# 20230822.net
KiCad netlist of a schematic drawn in EAGLE
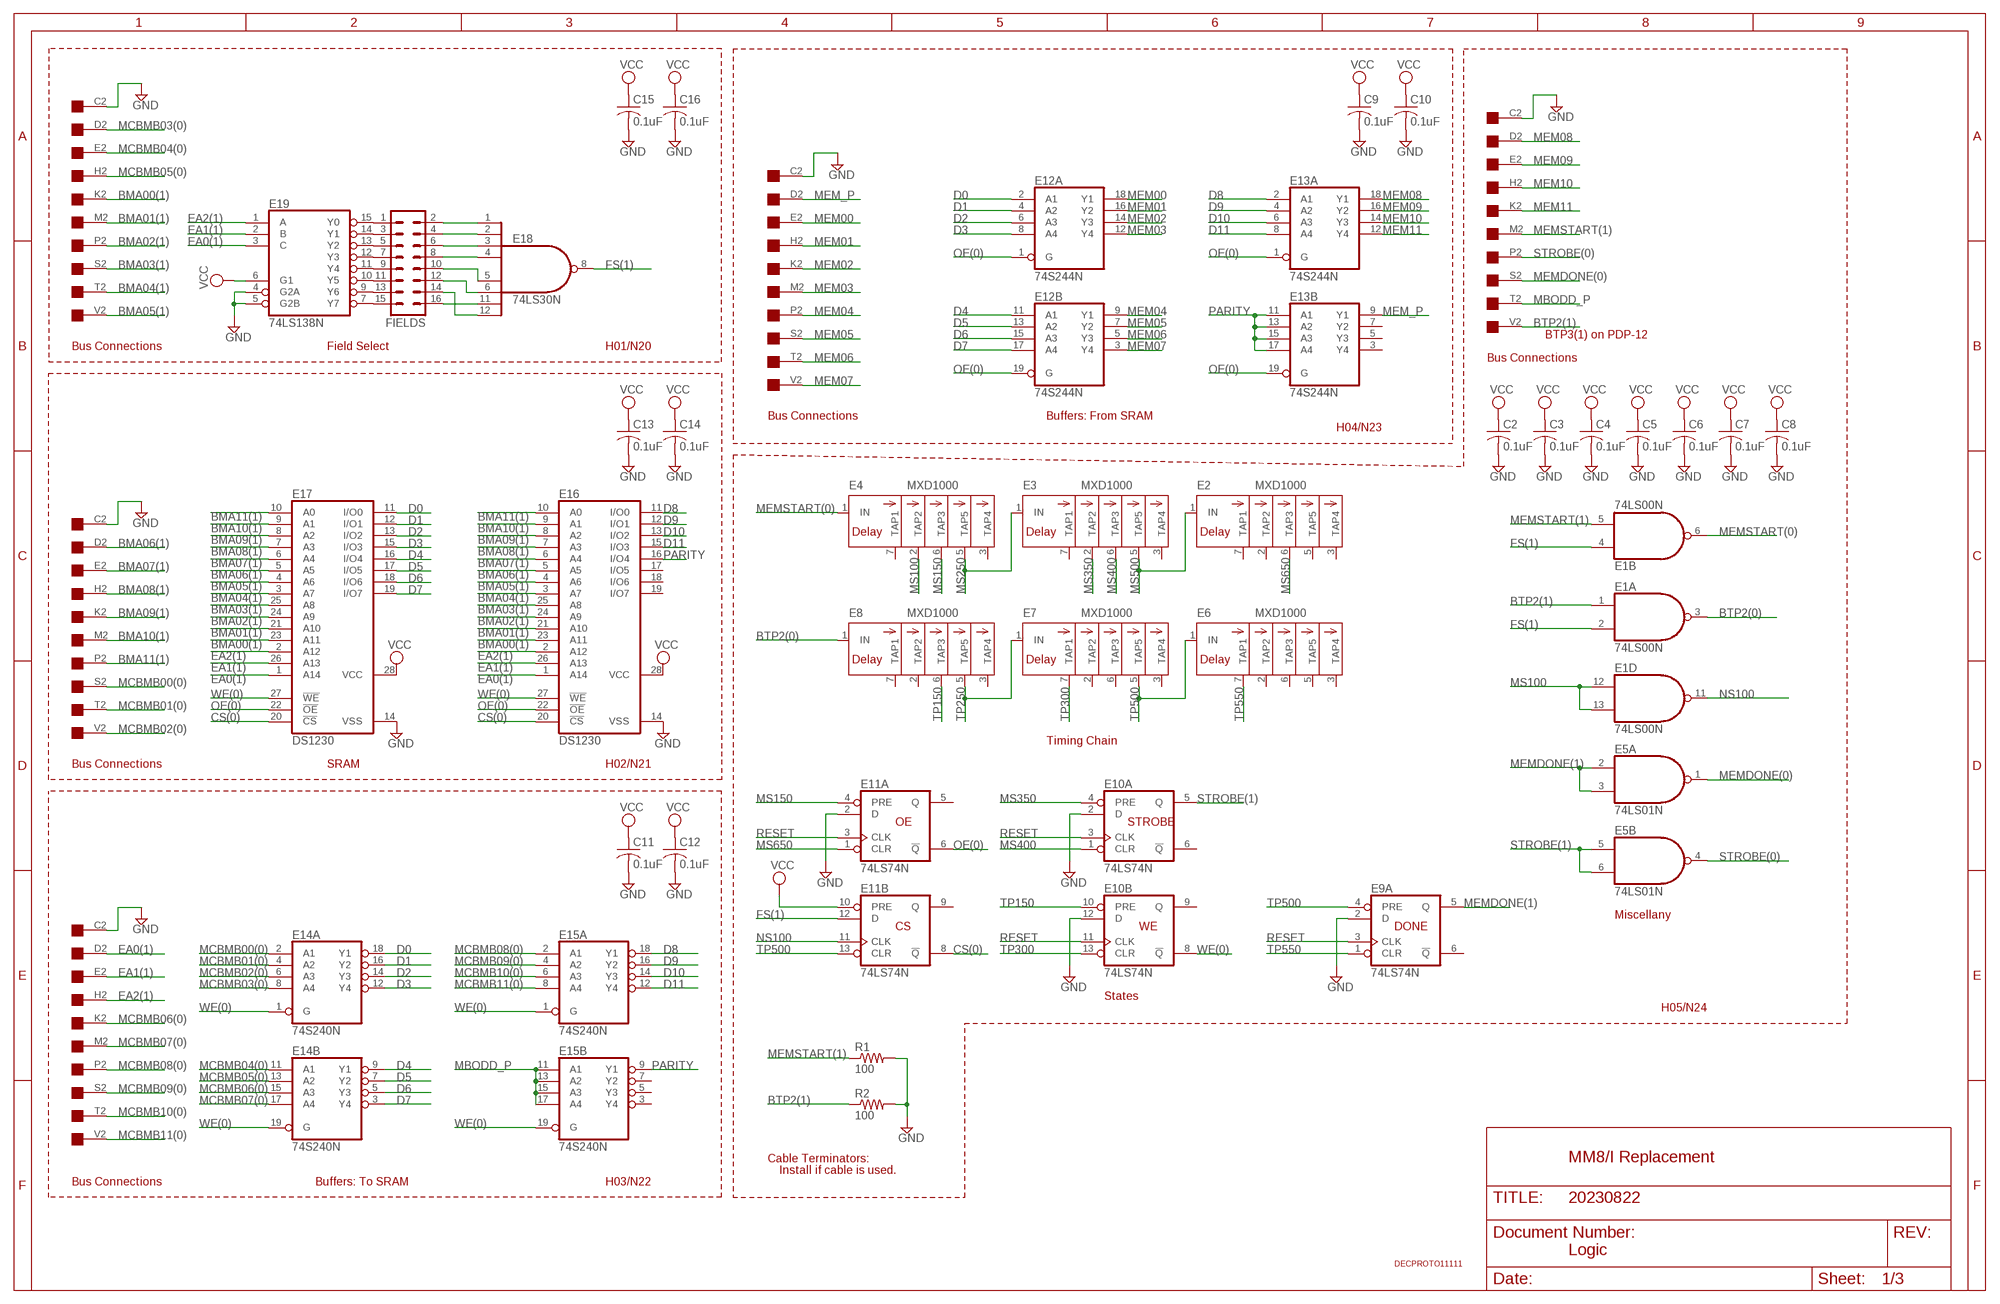
[diagram p0: schematic, sheet 1]
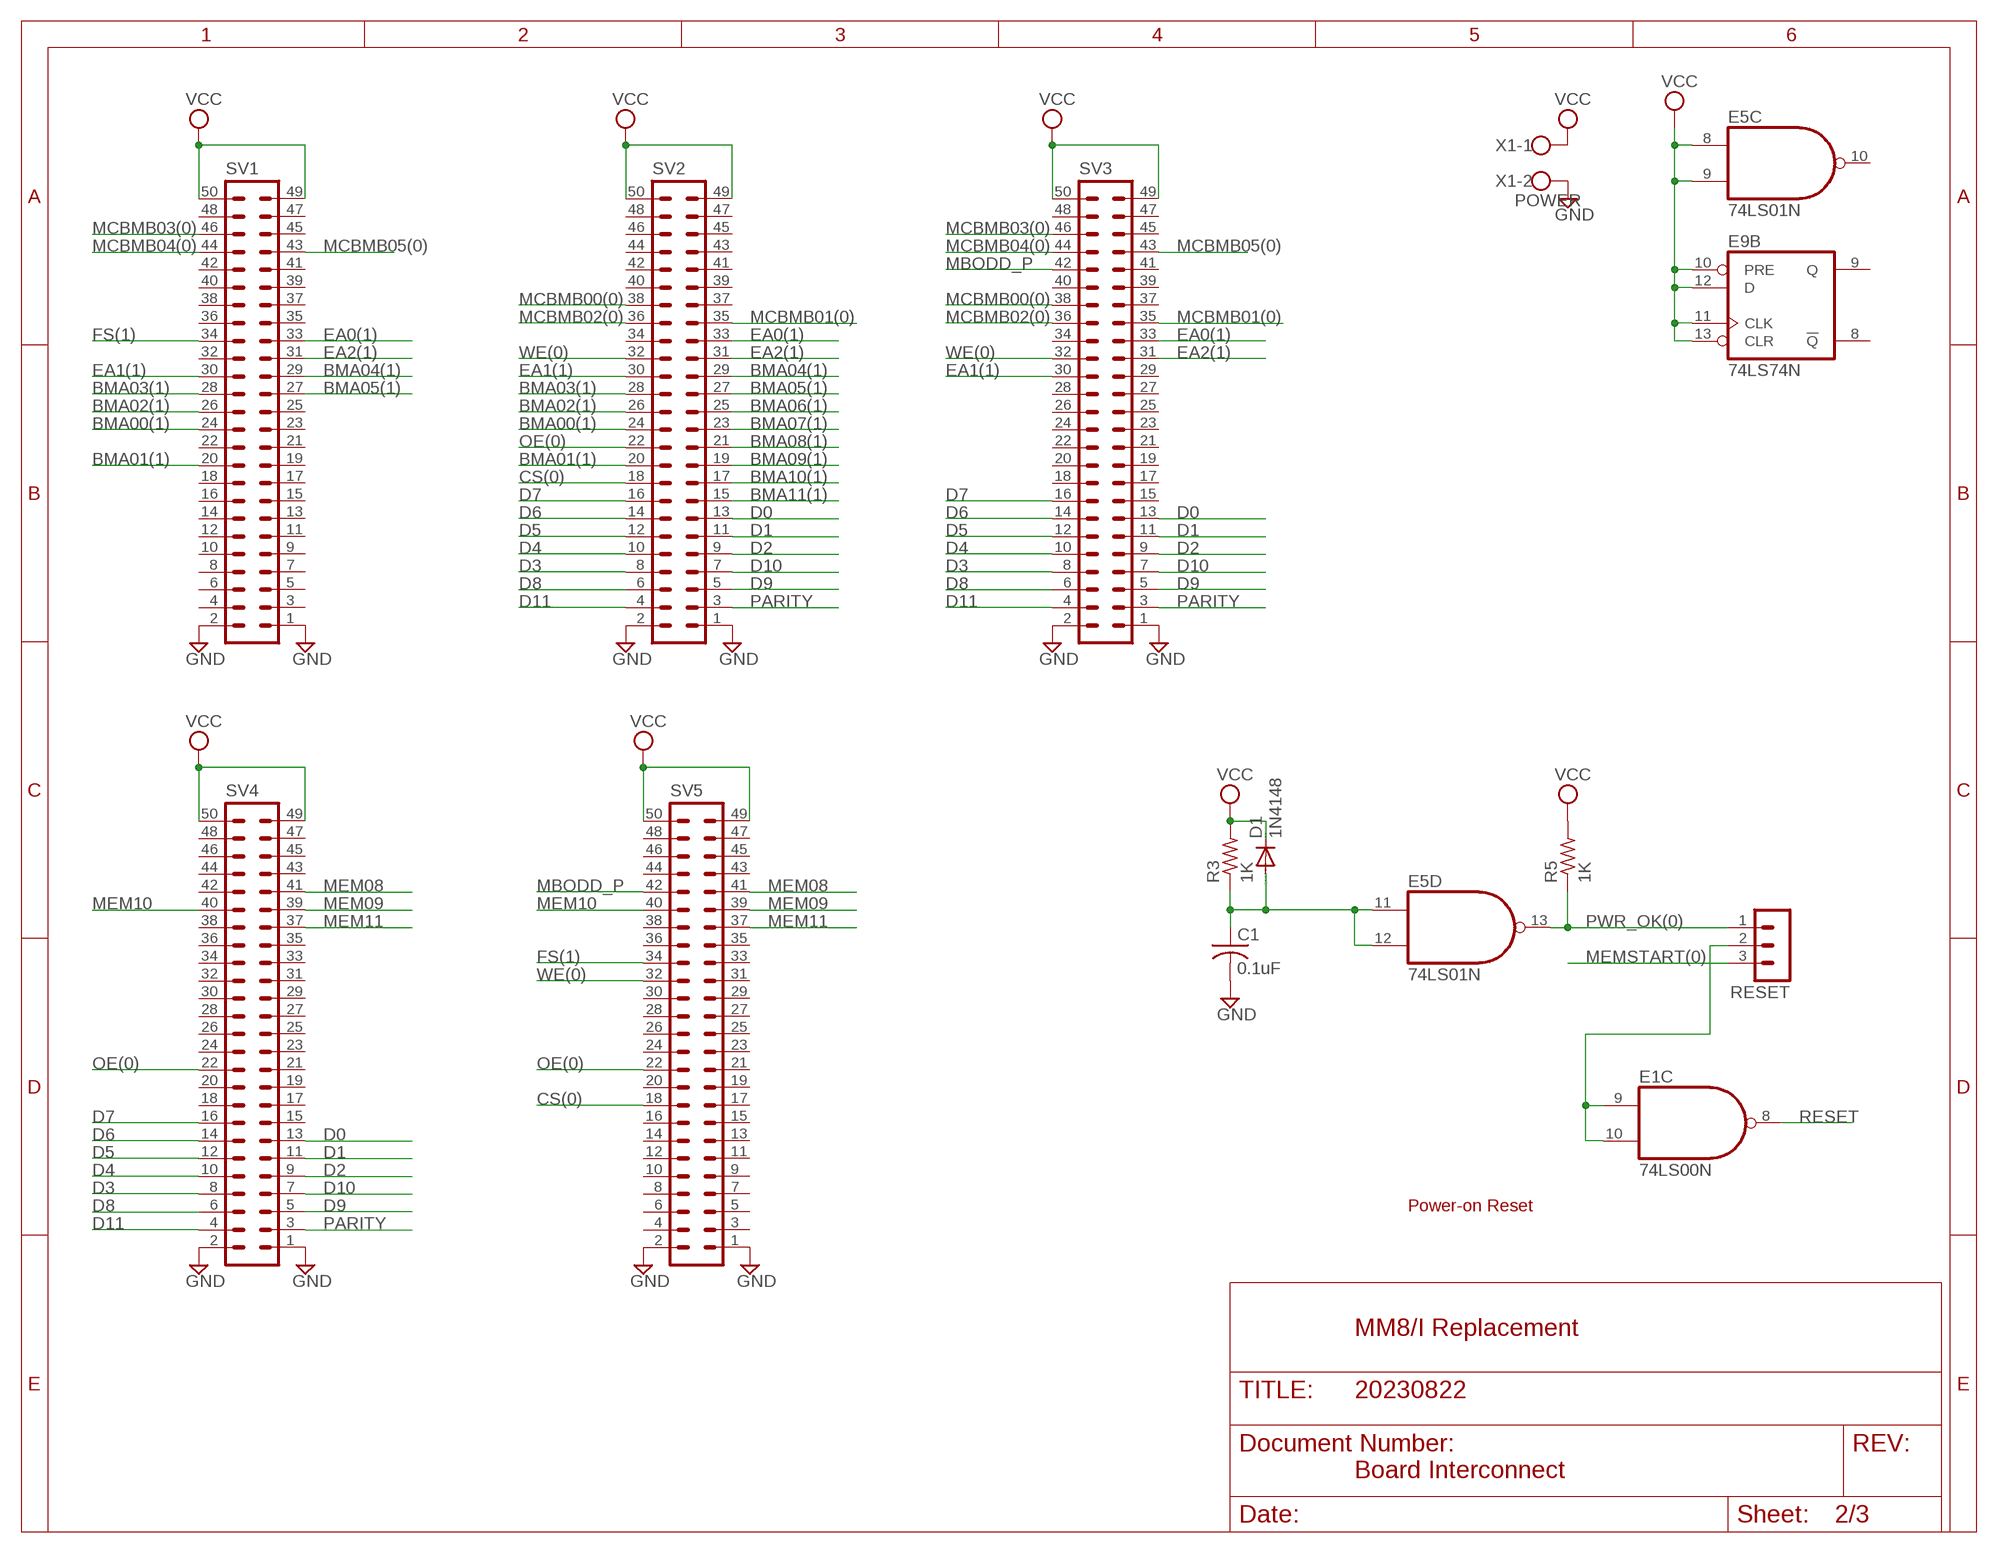
[diagram p1: schematic, sheet 2]
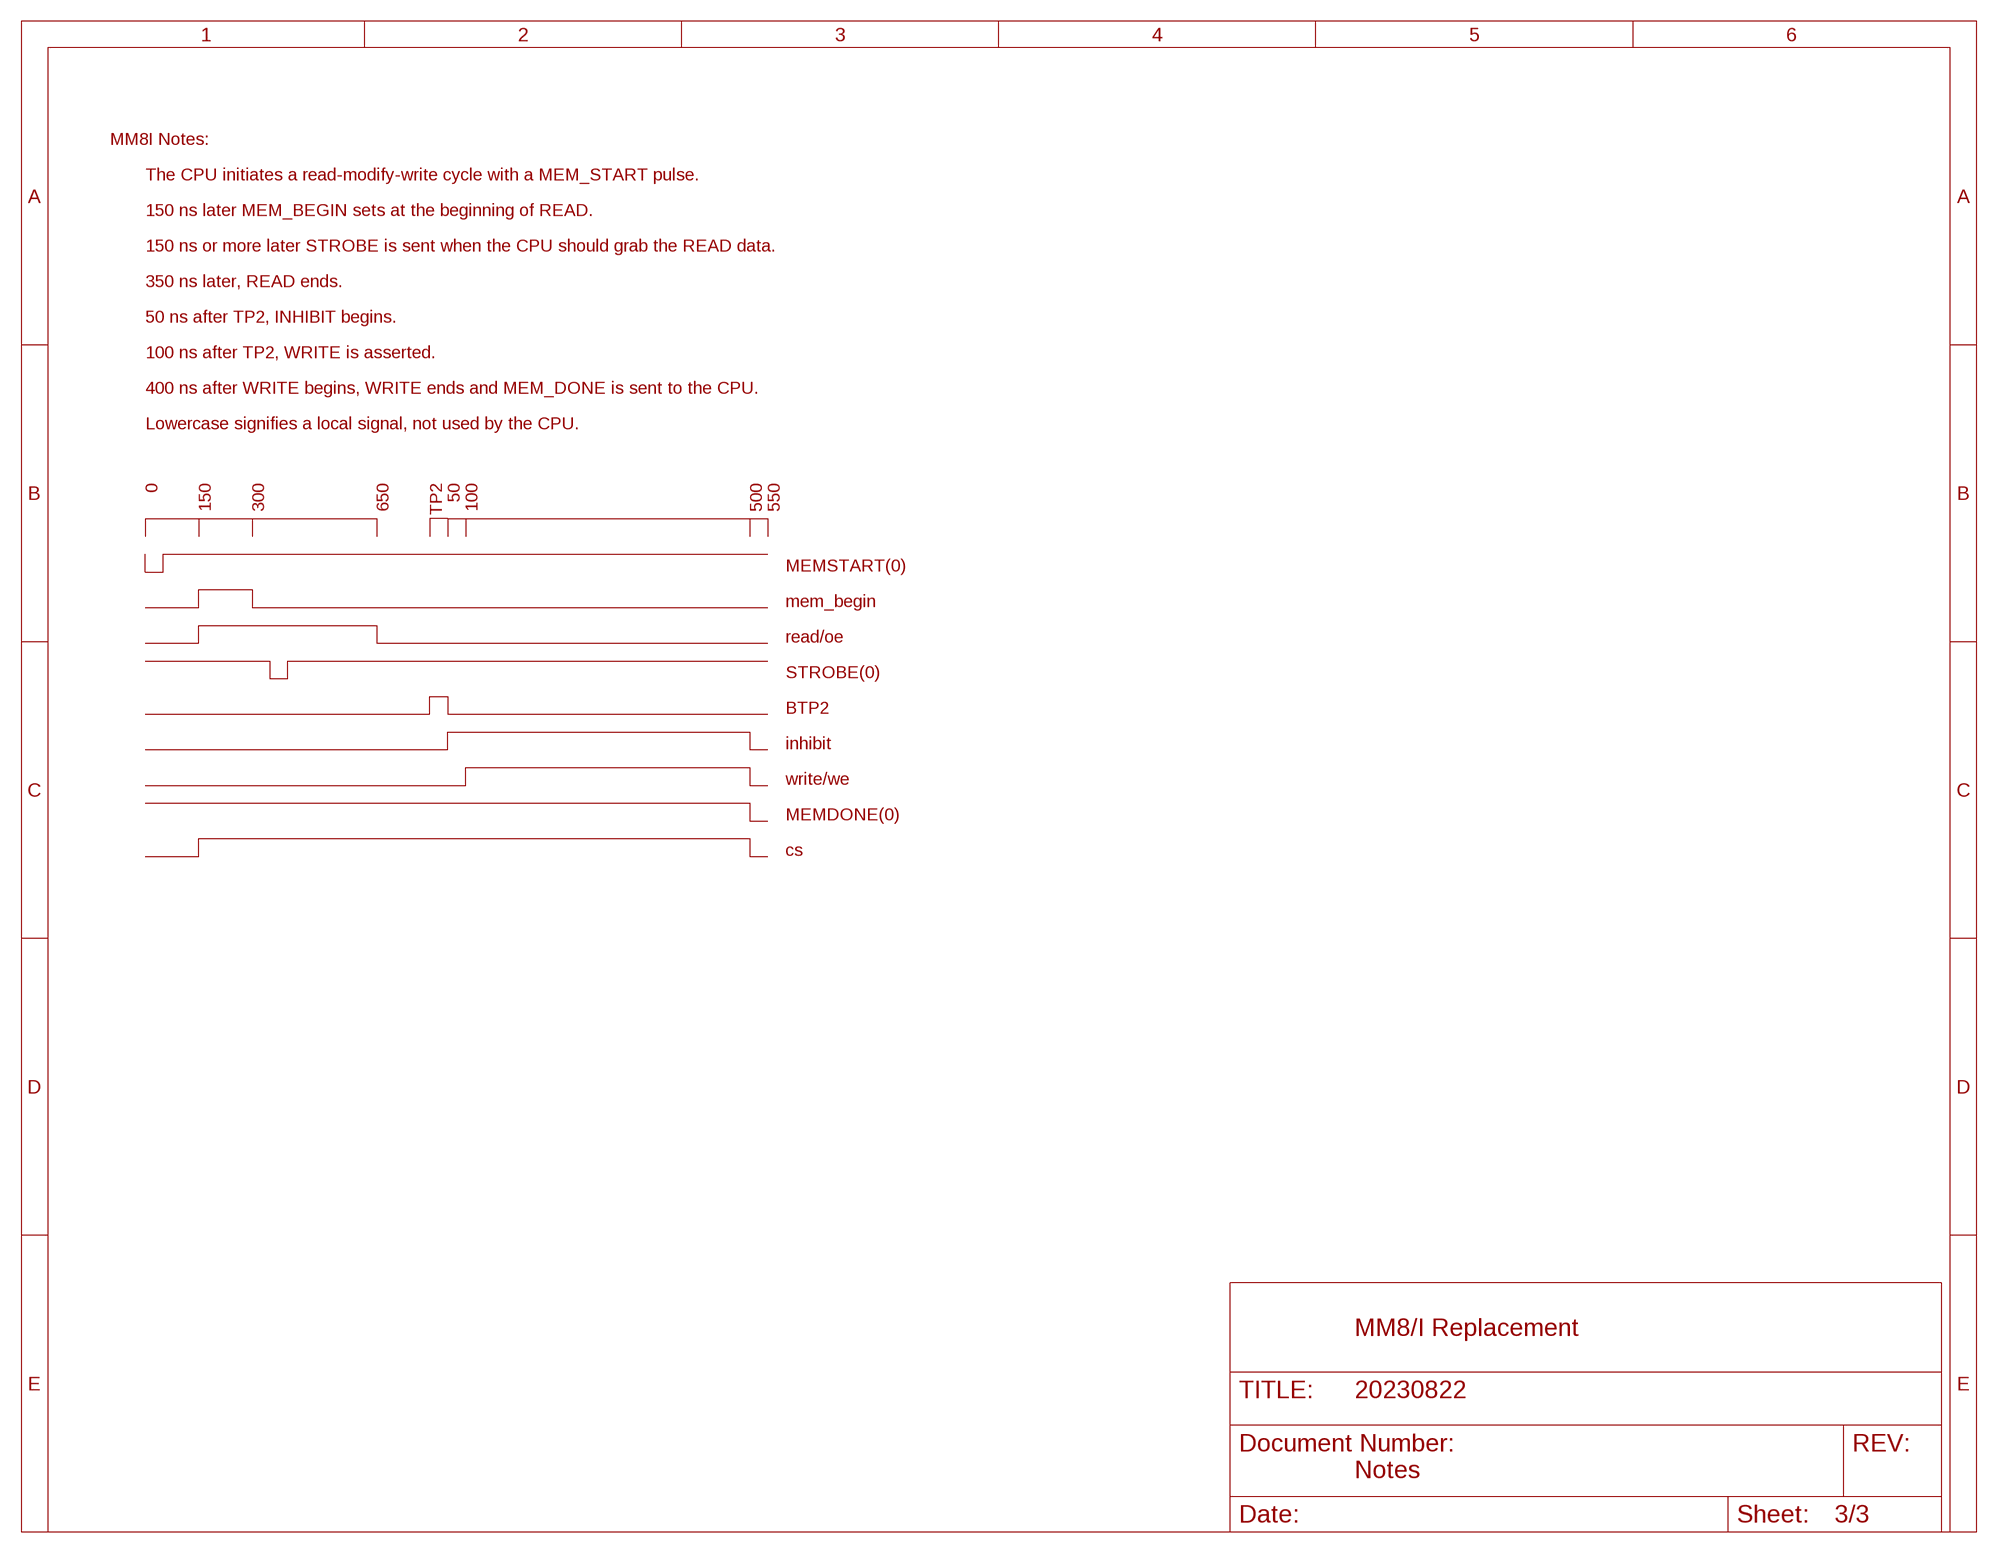
[diagram p2: schematic, sheet 3]

(export (version "E")
  (design (tool "Eeschema 10.0.6"))
  (components
    (comp (ref "C2")
      (value "0.1uF")
      (footprint "eagle-import:C050-025X075")
      (libsource (lib "eagle-import") (part "C-US050-025X075"))
    )
    (comp (ref "C3")
      (value "0.1uF")
      (footprint "eagle-import:C050-025X075")
      (libsource (lib "eagle-import") (part "C-US050-025X075"))
    )
    (comp (ref "C4")
      (value "0.1uF")
      (footprint "eagle-import:C050-025X075")
      (libsource (lib "eagle-import") (part "C-US050-025X075"))
    )
    (comp (ref "C5")
      (value "0.1uF")
      (footprint "eagle-import:C050-025X075")
      (libsource (lib "eagle-import") (part "C-US050-025X075"))
    )
    (comp (ref "C6")
      (value "0.1uF")
      (footprint "eagle-import:C050-025X075")
      (libsource (lib "eagle-import") (part "C-US050-025X075"))
    )
    (comp (ref "C7")
      (value "0.1uF")
      (footprint "eagle-import:C050-025X075")
      (libsource (lib "eagle-import") (part "C-US050-025X075"))
    )
    (comp (ref "C8")
      (value "0.1uF")
      (footprint "eagle-import:C050-025X075")
      (libsource (lib "eagle-import") (part "C-US050-025X075"))
    )
    (comp (ref "C9")
      (value "0.1uF")
      (footprint "eagle-import:C050-025X075")
      (libsource (lib "eagle-import") (part "C-US050-025X075"))
    )
    (comp (ref "C10")
      (value "0.1uF")
      (footprint "eagle-import:C050-025X075")
      (libsource (lib "eagle-import") (part "C-US050-025X075"))
    )
    (comp (ref "C11")
      (value "0.1uF")
      (footprint "eagle-import:C050-025X075")
      (libsource (lib "eagle-import") (part "C-US050-025X075"))
    )
    (comp (ref "C12")
      (value "0.1uF")
      (footprint "eagle-import:C050-025X075")
      (libsource (lib "eagle-import") (part "C-US050-025X075"))
    )
    (comp (ref "C13")
      (value "0.1uF")
      (footprint "eagle-import:C050-025X075")
      (libsource (lib "eagle-import") (part "C-US050-025X075"))
    )
    (comp (ref "C14")
      (value "0.1uF")
      (footprint "eagle-import:C050-025X075")
      (libsource (lib "eagle-import") (part "C-US050-025X075"))
    )
    (comp (ref "C15")
      (value "0.1uF")
      (footprint "eagle-import:C050-025X075")
      (libsource (lib "eagle-import") (part "C-US050-025X075"))
    )
    (comp (ref "C16")
      (value "0.1uF")
      (footprint "eagle-import:C050-025X075")
      (libsource (lib "eagle-import") (part "C-US050-025X075"))
    )
    (comp (ref "E1")
      (value "74LS00N")
      (footprint "eagle-import:DIL14")
      (libsource (lib "eagle-import") (part "7400NLS"))
    )
    (comp (ref "E2")
      (value "MXD1000")
      (footprint "eagle-import:DIL08")
      (libsource (lib "eagle-import") (part "MXD1000"))
    )
    (comp (ref "E3")
      (value "MXD1000")
      (footprint "eagle-import:DIL08")
      (libsource (lib "eagle-import") (part "MXD1000"))
    )
    (comp (ref "E4")
      (value "MXD1000")
      (footprint "eagle-import:DIL08")
      (libsource (lib "eagle-import") (part "MXD1000"))
    )
    (comp (ref "E5")
      (value "74LS01N")
      (footprint "eagle-import:DIL14")
      (libsource (lib "eagle-import") (part "7401NLS"))
    )
    (comp (ref "E6")
      (value "MXD1000")
      (footprint "eagle-import:DIL08")
      (libsource (lib "eagle-import") (part "MXD1000"))
    )
    (comp (ref "E7")
      (value "MXD1000")
      (footprint "eagle-import:DIL08")
      (libsource (lib "eagle-import") (part "MXD1000"))
    )
    (comp (ref "E8")
      (value "MXD1000")
      (footprint "eagle-import:DIL08")
      (libsource (lib "eagle-import") (part "MXD1000"))
    )
    (comp (ref "E9")
      (value "74LS74N")
      (footprint "eagle-import:DIL14")
      (libsource (lib "eagle-import") (part "7474NLS"))
    )
    (comp (ref "E10")
      (value "74LS74N")
      (footprint "eagle-import:DIL14")
      (libsource (lib "eagle-import") (part "7474NLS"))
    )
    (comp (ref "E11")
      (value "74LS74N")
      (footprint "eagle-import:DIL14")
      (libsource (lib "eagle-import") (part "7474NLS"))
    )
    (comp (ref "E12")
      (value "74S244N")
      (footprint "eagle-import:DIL20")
      (libsource (lib "eagle-import") (part "74244NS"))
    )
    (comp (ref "E13")
      (value "74S244N")
      (footprint "eagle-import:DIL20")
      (libsource (lib "eagle-import") (part "74244NS"))
    )
    (comp (ref "E14")
      (value "74S240N")
      (footprint "eagle-import:DIL20")
      (libsource (lib "eagle-import") (part "74240NS"))
    )
    (comp (ref "E15")
      (value "74S240N")
      (footprint "eagle-import:DIL20")
      (libsource (lib "eagle-import") (part "74240NS"))
    )
    (comp (ref "E16")
      (value "DS1230")
      (footprint "eagle-import:DIL28-6")
      (libsource (lib "eagle-import") (part "62256P"))
    )
    (comp (ref "E17")
      (value "DS1230")
      (footprint "eagle-import:DIL28-6")
      (libsource (lib "eagle-import") (part "62256P"))
    )
    (comp (ref "E18")
      (value "74LS30N")
      (footprint "eagle-import:DIL14")
      (libsource (lib "eagle-import") (part "7430NLS"))
    )
    (comp (ref "E19")
      (value "74LS138N")
      (footprint "eagle-import:DIL16")
      (libsource (lib "eagle-import") (part "74138NLS"))
    )
    (comp (ref "FIELDS")
      (value "MA08-2")
      (footprint "eagle-import:MA08-2")
      (libsource (lib "eagle-import") (part "MA08-2"))
    )
    (comp (ref "H01")
      (value "EDGE-1")
      (footprint "eagle-import:EDGE-CON1")
      (libsource (lib "eagle-import") (part "EDGE-1"))
    )
    (comp (ref "H02")
      (value "EDGE-1")
      (footprint "eagle-import:EDGE-CON1")
      (libsource (lib "eagle-import") (part "EDGE-1"))
    )
    (comp (ref "H03")
      (value "EDGE-1")
      (footprint "eagle-import:EDGE-CON1")
      (libsource (lib "eagle-import") (part "EDGE-1"))
    )
    (comp (ref "H04")
      (value "EDGE-1")
      (footprint "eagle-import:EDGE-CON1")
      (libsource (lib "eagle-import") (part "EDGE-1"))
    )
    (comp (ref "H05")
      (value "EDGE-1")
      (footprint "eagle-import:EDGE-CON1")
      (libsource (lib "eagle-import") (part "EDGE-1"))
    )
    (comp (ref "R1")
      (value "100")
      (footprint "eagle-import:0207_10")
      (libsource (lib "eagle-import") (part "R-US_0207/10"))
    )
    (comp (ref "R2")
      (value "100")
      (footprint "eagle-import:0207_10")
      (libsource (lib "eagle-import") (part "R-US_0207/10"))
    )
    (comp (ref "U$6")
      (value "DECPROTO11111")
      (footprint "eagle-import:DECPROTO11111")
      (libsource (lib "eagle-import") (part "DECPROTO11111"))
    )
    (comp (ref "C1")
      (value "0.1uF")
      (footprint "eagle-import:C050-025X075")
      (libsource (lib "eagle-import") (part "C-US050-025X075"))
    )
    (comp (ref "D1")
      (value "1N4148")
      (footprint "eagle-import:DO35-10")
      (libsource (lib "eagle-import") (part "1N4148DO35-10"))
    )
    (comp (ref "R3")
      (value "1K")
      (footprint "eagle-import:0207_10")
      (libsource (lib "eagle-import") (part "R-US_0207/10"))
    )
    (comp (ref "R5")
      (value "1K")
      (footprint "eagle-import:0207_10")
      (libsource (lib "eagle-import") (part "R-US_0207/10"))
    )
    (comp (ref "RESET")
      (value "MA03-1")
      (footprint "eagle-import:MA03-1")
      (libsource (lib "eagle-import") (part "MA03-1"))
    )
    (comp (ref "SV1")
      (value "ML50L")
      (footprint "eagle-import:ML50L")
      (libsource (lib "eagle-import") (part "ML50L"))
    )
    (comp (ref "SV2")
      (value "ML50L")
      (footprint "eagle-import:ML50L")
      (libsource (lib "eagle-import") (part "ML50L"))
    )
    (comp (ref "SV3")
      (value "ML50L")
      (footprint "eagle-import:ML50L")
      (libsource (lib "eagle-import") (part "ML50L"))
    )
    (comp (ref "SV4")
      (value "ML50L")
      (footprint "eagle-import:ML50L")
      (libsource (lib "eagle-import") (part "ML50L"))
    )
    (comp (ref "SV5")
      (value "ML50L")
      (footprint "eagle-import:ML50L")
      (libsource (lib "eagle-import") (part "ML50L"))
    )
    (comp (ref "X1")
      (value "POWER")
      (footprint "eagle-import:W237-102")
      (fields (field (name "MPN") "237-102"))
      (libsource (lib "eagle-import") (part "W237-102"))
    )
  )
  (nets
    (net (code "1") (name "BMA00(1)") (class "Default")
      (node (ref "E16") (pin "23") (pinfunction "A11_23") (pintype "input"))
      (node (ref "E17") (pin "23") (pinfunction "A11_23") (pintype "input"))
      (node (ref "H01") (pin "K2") (pinfunction "1_K2") (pintype "bidirectional"))
      (node (ref "SV1") (pin "24") (pinfunction "24_24") (pintype "passive"))
      (node (ref "SV2") (pin "24") (pinfunction "24_24") (pintype "passive"))
    )
    (net (code "2") (name "BMA01(1)") (class "Default")
      (node (ref "E16") (pin "21") (pinfunction "A10_21") (pintype "input"))
      (node (ref "E17") (pin "21") (pinfunction "A10_21") (pintype "input"))
      (node (ref "H01") (pin "M2") (pinfunction "1_M2") (pintype "bidirectional"))
      (node (ref "SV1") (pin "20") (pinfunction "20_20") (pintype "passive"))
      (node (ref "SV2") (pin "20") (pinfunction "20_20") (pintype "passive"))
    )
    (net (code "3") (name "BMA02(1)") (class "Default")
      (node (ref "E16") (pin "24") (pinfunction "A9_24") (pintype "input"))
      (node (ref "E17") (pin "24") (pinfunction "A9_24") (pintype "input"))
      (node (ref "H01") (pin "P2") (pinfunction "1_P2") (pintype "bidirectional"))
      (node (ref "SV1") (pin "26") (pinfunction "26_26") (pintype "passive"))
      (node (ref "SV2") (pin "26") (pinfunction "26_26") (pintype "passive"))
    )
    (net (code "4") (name "BMA03(1)") (class "Default")
      (node (ref "E16") (pin "25") (pinfunction "A8_25") (pintype "input"))
      (node (ref "E17") (pin "25") (pinfunction "A8_25") (pintype "input"))
      (node (ref "H01") (pin "S2") (pinfunction "1_S2") (pintype "bidirectional"))
      (node (ref "SV1") (pin "28") (pinfunction "28_28") (pintype "passive"))
      (node (ref "SV2") (pin "28") (pinfunction "28_28") (pintype "passive"))
    )
    (net (code "5") (name "BMA04(1)") (class "Default")
      (node (ref "E16") (pin "3") (pinfunction "A7_3") (pintype "input"))
      (node (ref "E17") (pin "3") (pinfunction "A7_3") (pintype "input"))
      (node (ref "H01") (pin "T2") (pinfunction "1_T2") (pintype "bidirectional"))
      (node (ref "SV1") (pin "29") (pinfunction "29_29") (pintype "passive"))
      (node (ref "SV2") (pin "29") (pinfunction "29_29") (pintype "passive"))
    )
    (net (code "6") (name "BMA05(1)") (class "Default")
      (node (ref "E16") (pin "4") (pinfunction "A6_4") (pintype "input"))
      (node (ref "E17") (pin "4") (pinfunction "A6_4") (pintype "input"))
      (node (ref "H01") (pin "V2") (pinfunction "1_V2") (pintype "bidirectional"))
      (node (ref "SV1") (pin "27") (pinfunction "27_27") (pintype "passive"))
      (node (ref "SV2") (pin "27") (pinfunction "27_27") (pintype "passive"))
    )
    (net (code "7") (name "BMA06(1)") (class "Default")
      (node (ref "E16") (pin "5") (pinfunction "A5_5") (pintype "input"))
      (node (ref "E17") (pin "5") (pinfunction "A5_5") (pintype "input"))
      (node (ref "H02") (pin "D2") (pinfunction "1_D2") (pintype "bidirectional"))
      (node (ref "SV2") (pin "25") (pinfunction "25_25") (pintype "passive"))
    )
    (net (code "8") (name "BMA07(1)") (class "Default")
      (node (ref "E16") (pin "6") (pinfunction "A4_6") (pintype "input"))
      (node (ref "E17") (pin "6") (pinfunction "A4_6") (pintype "input"))
      (node (ref "H02") (pin "E2") (pinfunction "1_E2") (pintype "bidirectional"))
      (node (ref "SV2") (pin "23") (pinfunction "23_23") (pintype "passive"))
    )
    (net (code "9") (name "BMA08(1)") (class "Default")
      (node (ref "E16") (pin "7") (pinfunction "A3_7") (pintype "input"))
      (node (ref "E17") (pin "7") (pinfunction "A3_7") (pintype "input"))
      (node (ref "H02") (pin "H2") (pinfunction "1_H2") (pintype "bidirectional"))
      (node (ref "SV2") (pin "21") (pinfunction "21_21") (pintype "passive"))
    )
    (net (code "10") (name "BMA09(1)") (class "Default")
      (node (ref "E16") (pin "8") (pinfunction "A2_8") (pintype "input"))
      (node (ref "E17") (pin "8") (pinfunction "A2_8") (pintype "input"))
      (node (ref "H02") (pin "K2") (pinfunction "1_K2") (pintype "bidirectional"))
      (node (ref "SV2") (pin "19") (pinfunction "19_19") (pintype "passive"))
    )
    (net (code "11") (name "BMA10(1)") (class "Default")
      (node (ref "E16") (pin "9") (pinfunction "A1_9") (pintype "input"))
      (node (ref "E17") (pin "9") (pinfunction "A1_9") (pintype "input"))
      (node (ref "H02") (pin "M2") (pinfunction "1_M2") (pintype "bidirectional"))
      (node (ref "SV2") (pin "17") (pinfunction "17_17") (pintype "passive"))
    )
    (net (code "12") (name "BMA11(1)") (class "Default")
      (node (ref "E16") (pin "10") (pinfunction "A0_10") (pintype "input"))
      (node (ref "E17") (pin "10") (pinfunction "A0_10") (pintype "input"))
      (node (ref "H02") (pin "P2") (pinfunction "1_P2") (pintype "bidirectional"))
      (node (ref "SV2") (pin "15") (pinfunction "15_15") (pintype "passive"))
    )
    (net (code "13") (name "BTP2(0)") (class "Default")
      (node (ref "E1") (pin "3") (pinfunction "O_3") (pintype "output"))
      (node (ref "E8") (pin "1") (pinfunction "IN_1") (pintype "input"))
    )
    (net (code "14") (name "BTP2(1)") (class "Default")
      (node (ref "E1") (pin "1") (pinfunction "I0_1") (pintype "input"))
      (node (ref "H05") (pin "V2") (pinfunction "1_V2") (pintype "bidirectional"))
      (node (ref "R2") (pin "1") (pinfunction "1_1") (pintype "passive"))
    )
    (net (code "15") (name "CS(0)") (class "Default")
      (node (ref "E11") (pin "8") (pinfunction "~{Q}_8") (pintype "output"))
      (node (ref "E16") (pin "20") (pinfunction "~{CS}_20") (pintype "input"))
      (node (ref "E17") (pin "20") (pinfunction "~{CS}_20") (pintype "input"))
      (node (ref "SV2") (pin "18") (pinfunction "18_18") (pintype "passive"))
      (node (ref "SV5") (pin "18") (pinfunction "18_18") (pintype "passive"))
    )
    (net (code "16") (name "D0") (class "Default")
      (node (ref "E12") (pin "2") (pinfunction "A1_2") (pintype "input"))
      (node (ref "E14") (pin "18") (pinfunction "Y1_18") (pintype "tri_state"))
      (node (ref "E17") (pin "11") (pinfunction "I/O0_11") (pintype "bidirectional"))
      (node (ref "SV2") (pin "13") (pinfunction "13_13") (pintype "passive"))
      (node (ref "SV3") (pin "13") (pinfunction "13_13") (pintype "passive"))
      (node (ref "SV4") (pin "13") (pinfunction "13_13") (pintype "passive"))
    )
    (net (code "17") (name "D1") (class "Default")
      (node (ref "E12") (pin "4") (pinfunction "A2_4") (pintype "input"))
      (node (ref "E14") (pin "16") (pinfunction "Y2_16") (pintype "tri_state"))
      (node (ref "E17") (pin "12") (pinfunction "I/O1_12") (pintype "bidirectional"))
      (node (ref "SV2") (pin "11") (pinfunction "11_11") (pintype "passive"))
      (node (ref "SV3") (pin "11") (pinfunction "11_11") (pintype "passive"))
      (node (ref "SV4") (pin "11") (pinfunction "11_11") (pintype "passive"))
    )
    (net (code "18") (name "D2") (class "Default")
      (node (ref "E12") (pin "6") (pinfunction "A3_6") (pintype "input"))
      (node (ref "E14") (pin "14") (pinfunction "Y3_14") (pintype "tri_state"))
      (node (ref "E17") (pin "13") (pinfunction "I/O2_13") (pintype "bidirectional"))
      (node (ref "SV2") (pin "9") (pinfunction "9_9") (pintype "passive"))
      (node (ref "SV3") (pin "9") (pinfunction "9_9") (pintype "passive"))
      (node (ref "SV4") (pin "9") (pinfunction "9_9") (pintype "passive"))
    )
    (net (code "19") (name "D3") (class "Default")
      (node (ref "E12") (pin "8") (pinfunction "A4_8") (pintype "input"))
      (node (ref "E14") (pin "12") (pinfunction "Y4_12") (pintype "tri_state"))
      (node (ref "E17") (pin "15") (pinfunction "I/O3_15") (pintype "bidirectional"))
      (node (ref "SV2") (pin "8") (pinfunction "8_8") (pintype "passive"))
      (node (ref "SV3") (pin "8") (pinfunction "8_8") (pintype "passive"))
      (node (ref "SV4") (pin "8") (pinfunction "8_8") (pintype "passive"))
    )
    (net (code "20") (name "D4") (class "Default")
      (node (ref "E12") (pin "11") (pinfunction "A1_11") (pintype "input"))
      (node (ref "E14") (pin "9") (pinfunction "Y1_9") (pintype "tri_state"))
      (node (ref "E17") (pin "16") (pinfunction "I/O4_16") (pintype "bidirectional"))
      (node (ref "SV2") (pin "10") (pinfunction "10_10") (pintype "passive"))
      (node (ref "SV3") (pin "10") (pinfunction "10_10") (pintype "passive"))
      (node (ref "SV4") (pin "10") (pinfunction "10_10") (pintype "passive"))
    )
    (net (code "21") (name "D5") (class "Default")
      (node (ref "E12") (pin "13") (pinfunction "A2_13") (pintype "input"))
      (node (ref "E14") (pin "7") (pinfunction "Y2_7") (pintype "tri_state"))
      (node (ref "E17") (pin "17") (pinfunction "I/O5_17") (pintype "bidirectional"))
      (node (ref "SV2") (pin "12") (pinfunction "12_12") (pintype "passive"))
      (node (ref "SV3") (pin "12") (pinfunction "12_12") (pintype "passive"))
      (node (ref "SV4") (pin "12") (pinfunction "12_12") (pintype "passive"))
    )
    (net (code "22") (name "D6") (class "Default")
      (node (ref "E12") (pin "15") (pinfunction "A3_15") (pintype "input"))
      (node (ref "E14") (pin "5") (pinfunction "Y3_5") (pintype "tri_state"))
      (node (ref "E17") (pin "18") (pinfunction "I/O6_18") (pintype "bidirectional"))
      (node (ref "SV2") (pin "14") (pinfunction "14_14") (pintype "passive"))
      (node (ref "SV3") (pin "14") (pinfunction "14_14") (pintype "passive"))
      (node (ref "SV4") (pin "14") (pinfunction "14_14") (pintype "passive"))
    )
    (net (code "23") (name "D7") (class "Default")
      (node (ref "E12") (pin "17") (pinfunction "A4_17") (pintype "input"))
      (node (ref "E14") (pin "3") (pinfunction "Y4_3") (pintype "tri_state"))
      (node (ref "E17") (pin "19") (pinfunction "I/O7_19") (pintype "bidirectional"))
      (node (ref "SV2") (pin "16") (pinfunction "16_16") (pintype "passive"))
      (node (ref "SV3") (pin "16") (pinfunction "16_16") (pintype "passive"))
      (node (ref "SV4") (pin "16") (pinfunction "16_16") (pintype "passive"))
    )
    (net (code "24") (name "D8") (class "Default")
      (node (ref "E13") (pin "2") (pinfunction "A1_2") (pintype "input"))
      (node (ref "E15") (pin "18") (pinfunction "Y1_18") (pintype "tri_state"))
      (node (ref "E16") (pin "11") (pinfunction "I/O0_11") (pintype "bidirectional"))
      (node (ref "SV2") (pin "6") (pinfunction "6_6") (pintype "passive"))
      (node (ref "SV3") (pin "6") (pinfunction "6_6") (pintype "passive"))
      (node (ref "SV4") (pin "6") (pinfunction "6_6") (pintype "passive"))
    )
    (net (code "25") (name "D9") (class "Default")
      (node (ref "E13") (pin "4") (pinfunction "A2_4") (pintype "input"))
      (node (ref "E15") (pin "16") (pinfunction "Y2_16") (pintype "tri_state"))
      (node (ref "E16") (pin "12") (pinfunction "I/O1_12") (pintype "bidirectional"))
      (node (ref "SV2") (pin "5") (pinfunction "5_5") (pintype "passive"))
      (node (ref "SV3") (pin "5") (pinfunction "5_5") (pintype "passive"))
      (node (ref "SV4") (pin "5") (pinfunction "5_5") (pintype "passive"))
    )
    (net (code "26") (name "D10") (class "Default")
      (node (ref "E13") (pin "6") (pinfunction "A3_6") (pintype "input"))
      (node (ref "E15") (pin "14") (pinfunction "Y3_14") (pintype "tri_state"))
      (node (ref "E16") (pin "13") (pinfunction "I/O2_13") (pintype "bidirectional"))
      (node (ref "SV2") (pin "7") (pinfunction "7_7") (pintype "passive"))
      (node (ref "SV3") (pin "7") (pinfunction "7_7") (pintype "passive"))
      (node (ref "SV4") (pin "7") (pinfunction "7_7") (pintype "passive"))
    )
    (net (code "27") (name "D11") (class "Default")
      (node (ref "E13") (pin "8") (pinfunction "A4_8") (pintype "input"))
      (node (ref "E15") (pin "12") (pinfunction "Y4_12") (pintype "tri_state"))
      (node (ref "E16") (pin "15") (pinfunction "I/O3_15") (pintype "bidirectional"))
      (node (ref "SV2") (pin "4") (pinfunction "4_4") (pintype "passive"))
      (node (ref "SV3") (pin "4") (pinfunction "4_4") (pintype "passive"))
      (node (ref "SV4") (pin "4") (pinfunction "4_4") (pintype "passive"))
    )
    (net (code "28") (name "EA0(1)") (class "Default")
      (node (ref "E16") (pin "1") (pinfunction "A14_1") (pintype "input"))
      (node (ref "E17") (pin "1") (pinfunction "A14_1") (pintype "input"))
      (node (ref "E19") (pin "3") (pinfunction "C_3") (pintype "input"))
      (node (ref "H03") (pin "D2") (pinfunction "1_D2") (pintype "bidirectional"))
      (node (ref "SV1") (pin "33") (pinfunction "33_33") (pintype "passive"))
      (node (ref "SV2") (pin "33") (pinfunction "33_33") (pintype "passive"))
      (node (ref "SV3") (pin "33") (pinfunction "33_33") (pintype "passive"))
    )
    (net (code "29") (name "EA1(1)") (class "Default")
      (node (ref "E16") (pin "26") (pinfunction "A13_26") (pintype "input"))
      (node (ref "E17") (pin "26") (pinfunction "A13_26") (pintype "input"))
      (node (ref "E19") (pin "2") (pinfunction "B_2") (pintype "input"))
      (node (ref "H03") (pin "E2") (pinfunction "1_E2") (pintype "bidirectional"))
      (node (ref "SV1") (pin "30") (pinfunction "30_30") (pintype "passive"))
      (node (ref "SV2") (pin "30") (pinfunction "30_30") (pintype "passive"))
      (node (ref "SV3") (pin "30") (pinfunction "30_30") (pintype "passive"))
    )
    (net (code "30") (name "EA2(1)") (class "Default")
      (node (ref "E16") (pin "2") (pinfunction "A12_2") (pintype "input"))
      (node (ref "E17") (pin "2") (pinfunction "A12_2") (pintype "input"))
      (node (ref "E19") (pin "1") (pinfunction "A_1") (pintype "input"))
      (node (ref "H03") (pin "H2") (pinfunction "1_H2") (pintype "bidirectional"))
      (node (ref "SV1") (pin "31") (pinfunction "31_31") (pintype "passive"))
      (node (ref "SV2") (pin "31") (pinfunction "31_31") (pintype "passive"))
      (node (ref "SV3") (pin "31") (pinfunction "31_31") (pintype "passive"))
    )
    (net (code "31") (name "FS(1)") (class "Default")
      (node (ref "E1") (pin "2") (pinfunction "I1_2") (pintype "input"))
      (node (ref "E1") (pin "4") (pinfunction "I0_4") (pintype "input"))
      (node (ref "E11") (pin "12") (pinfunction "D_12") (pintype "input"))
      (node (ref "E18") (pin "8") (pinfunction "O_8") (pintype "output"))
      (node (ref "SV1") (pin "34") (pinfunction "34_34") (pintype "passive"))
      (node (ref "SV5") (pin "34") (pinfunction "34_34") (pintype "passive"))
    )
    (net (code "32") (name "GND") (class "Default")
      (node (ref "C1") (pin "2") (pinfunction "2_2") (pintype "passive"))
      (node (ref "C10") (pin "2") (pinfunction "2_2") (pintype "passive"))
      (node (ref "C11") (pin "2") (pinfunction "2_2") (pintype "passive"))
      (node (ref "C12") (pin "2") (pinfunction "2_2") (pintype "passive"))
      (node (ref "C13") (pin "2") (pinfunction "2_2") (pintype "passive"))
      (node (ref "C14") (pin "2") (pinfunction "2_2") (pintype "passive"))
      (node (ref "C15") (pin "2") (pinfunction "2_2") (pintype "passive"))
      (node (ref "C16") (pin "2") (pinfunction "2_2") (pintype "passive"))
      (node (ref "C2") (pin "2") (pinfunction "2_2") (pintype "passive"))
      (node (ref "C3") (pin "2") (pinfunction "2_2") (pintype "passive"))
      (node (ref "C4") (pin "2") (pinfunction "2_2") (pintype "passive"))
      (node (ref "C5") (pin "2") (pinfunction "2_2") (pintype "passive"))
      (node (ref "C6") (pin "2") (pinfunction "2_2") (pintype "passive"))
      (node (ref "C7") (pin "2") (pinfunction "2_2") (pintype "passive"))
      (node (ref "C8") (pin "2") (pinfunction "2_2") (pintype "passive"))
      (node (ref "C9") (pin "2") (pinfunction "2_2") (pintype "passive"))
      (node (ref "E10") (pin "12") (pinfunction "D_12") (pintype "input"))
      (node (ref "E10") (pin "2") (pinfunction "D_2") (pintype "input"))
      (node (ref "E11") (pin "2") (pinfunction "D_2") (pintype "input"))
      (node (ref "E16") (pin "14") (pinfunction "VSS_14") (pintype "power_in"))
      (node (ref "E17") (pin "14") (pinfunction "VSS_14") (pintype "power_in"))
      (node (ref "E19") (pin "4") (pinfunction "G2A_4") (pintype "input"))
      (node (ref "E19") (pin "5") (pinfunction "G2B_5") (pintype "input"))
      (node (ref "E9") (pin "2") (pinfunction "D_2") (pintype "input"))
      (node (ref "H01") (pin "C2") (pinfunction "1_C2") (pintype "bidirectional"))
      (node (ref "H02") (pin "C2") (pinfunction "1_C2") (pintype "bidirectional"))
      (node (ref "H03") (pin "C2") (pinfunction "1_C2") (pintype "bidirectional"))
      (node (ref "H04") (pin "C2") (pinfunction "1_C2") (pintype "bidirectional"))
      (node (ref "H05") (pin "C2") (pinfunction "1_C2") (pintype "bidirectional"))
      (node (ref "R1") (pin "2") (pinfunction "2_2") (pintype "passive"))
      (node (ref "R2") (pin "2") (pinfunction "2_2") (pintype "passive"))
      (node (ref "SV1") (pin "1") (pinfunction "1_1") (pintype "passive"))
      (node (ref "SV1") (pin "2") (pinfunction "2_2") (pintype "passive"))
      (node (ref "SV2") (pin "1") (pinfunction "1_1") (pintype "passive"))
      (node (ref "SV2") (pin "2") (pinfunction "2_2") (pintype "passive"))
      (node (ref "SV3") (pin "1") (pinfunction "1_1") (pintype "passive"))
      (node (ref "SV3") (pin "2") (pinfunction "2_2") (pintype "passive"))
      (node (ref "SV4") (pin "1") (pinfunction "1_1") (pintype "passive"))
      (node (ref "SV4") (pin "2") (pinfunction "2_2") (pintype "passive"))
      (node (ref "SV5") (pin "1") (pinfunction "1_1") (pintype "passive"))
      (node (ref "SV5") (pin "2") (pinfunction "2_2") (pintype "passive"))
      (node (ref "X1") (pin "2") (pinfunction "KL_2") (pintype "passive"))
    )
    (net (code "33") (name "MBODD_P") (class "Default")
      (node (ref "E15") (pin "11") (pinfunction "A1_11") (pintype "input"))
      (node (ref "E15") (pin "13") (pinfunction "A2_13") (pintype "input"))
      (node (ref "E15") (pin "15") (pinfunction "A3_15") (pintype "input"))
      (node (ref "E15") (pin "17") (pinfunction "A4_17") (pintype "input"))
      (node (ref "H05") (pin "T2") (pinfunction "1_T2") (pintype "bidirectional"))
      (node (ref "SV3") (pin "42") (pinfunction "42_42") (pintype "passive"))
      (node (ref "SV5") (pin "42") (pinfunction "42_42") (pintype "passive"))
    )
    (net (code "34") (name "MCBMB00(0)") (class "Default")
      (node (ref "E14") (pin "2") (pinfunction "A1_2") (pintype "input"))
      (node (ref "H02") (pin "S2") (pinfunction "1_S2") (pintype "bidirectional"))
      (node (ref "SV2") (pin "38") (pinfunction "38_38") (pintype "passive"))
      (node (ref "SV3") (pin "38") (pinfunction "38_38") (pintype "passive"))
    )
    (net (code "35") (name "MCBMB01(0)") (class "Default")
      (node (ref "E14") (pin "4") (pinfunction "A2_4") (pintype "input"))
      (node (ref "H02") (pin "T2") (pinfunction "1_T2") (pintype "bidirectional"))
      (node (ref "SV2") (pin "35") (pinfunction "35_35") (pintype "passive"))
      (node (ref "SV3") (pin "35") (pinfunction "35_35") (pintype "passive"))
    )
    (net (code "36") (name "MCBMB02(0)") (class "Default")
      (node (ref "E14") (pin "6") (pinfunction "A3_6") (pintype "input"))
      (node (ref "H02") (pin "V2") (pinfunction "1_V2") (pintype "bidirectional"))
      (node (ref "SV2") (pin "36") (pinfunction "36_36") (pintype "passive"))
      (node (ref "SV3") (pin "36") (pinfunction "36_36") (pintype "passive"))
    )
    (net (code "37") (name "MCBMB03(0)") (class "Default")
      (node (ref "E14") (pin "8") (pinfunction "A4_8") (pintype "input"))
      (node (ref "H01") (pin "D2") (pinfunction "1_D2") (pintype "bidirectional"))
      (node (ref "SV1") (pin "46") (pinfunction "46_46") (pintype "passive"))
      (node (ref "SV3") (pin "46") (pinfunction "46_46") (pintype "passive"))
    )
    (net (code "38") (name "MCBMB04(0)") (class "Default")
      (node (ref "E14") (pin "11") (pinfunction "A1_11") (pintype "input"))
      (node (ref "H01") (pin "E2") (pinfunction "1_E2") (pintype "bidirectional"))
      (node (ref "SV1") (pin "44") (pinfunction "44_44") (pintype "passive"))
      (node (ref "SV3") (pin "44") (pinfunction "44_44") (pintype "passive"))
    )
    (net (code "39") (name "MCBMB05(0)") (class "Default")
      (node (ref "E14") (pin "13") (pinfunction "A2_13") (pintype "input"))
      (node (ref "H01") (pin "H2") (pinfunction "1_H2") (pintype "bidirectional"))
      (node (ref "SV1") (pin "43") (pinfunction "43_43") (pintype "passive"))
      (node (ref "SV3") (pin "43") (pinfunction "43_43") (pintype "passive"))
    )
    (net (code "40") (name "MCBMB06(0)") (class "Default")
      (node (ref "E14") (pin "15") (pinfunction "A3_15") (pintype "input"))
      (node (ref "H03") (pin "K2") (pinfunction "1_K2") (pintype "bidirectional"))
    )
    (net (code "41") (name "MCBMB07(0)") (class "Default")
      (node (ref "E14") (pin "17") (pinfunction "A4_17") (pintype "input"))
      (node (ref "H03") (pin "M2") (pinfunction "1_M2") (pintype "bidirectional"))
    )
    (net (code "42") (name "MCBMB08(0)") (class "Default")
      (node (ref "E15") (pin "2") (pinfunction "A1_2") (pintype "input"))
      (node (ref "H03") (pin "P2") (pinfunction "1_P2") (pintype "bidirectional"))
    )
    (net (code "43") (name "MCBMB09(0)") (class "Default")
      (node (ref "E15") (pin "4") (pinfunction "A2_4") (pintype "input"))
      (node (ref "H03") (pin "S2") (pinfunction "1_S2") (pintype "bidirectional"))
    )
    (net (code "44") (name "MCBMB10(0)") (class "Default")
      (node (ref "E15") (pin "6") (pinfunction "A3_6") (pintype "input"))
      (node (ref "H03") (pin "T2") (pinfunction "1_T2") (pintype "bidirectional"))
    )
    (net (code "45") (name "MCBMB11(0)") (class "Default")
      (node (ref "E15") (pin "8") (pinfunction "A4_8") (pintype "input"))
      (node (ref "H03") (pin "V2") (pinfunction "1_V2") (pintype "bidirectional"))
    )
    (net (code "46") (name "MEM00") (class "Default")
      (node (ref "E12") (pin "18") (pinfunction "Y1_18") (pintype "tri_state"))
      (node (ref "H04") (pin "E2") (pinfunction "1_E2") (pintype "bidirectional"))
    )
    (net (code "47") (name "MEM01") (class "Default")
      (node (ref "E12") (pin "16") (pinfunction "Y2_16") (pintype "tri_state"))
      (node (ref "H04") (pin "H2") (pinfunction "1_H2") (pintype "bidirectional"))
    )
    (net (code "48") (name "MEM02") (class "Default")
      (node (ref "E12") (pin "14") (pinfunction "Y3_14") (pintype "tri_state"))
      (node (ref "H04") (pin "K2") (pinfunction "1_K2") (pintype "bidirectional"))
    )
    (net (code "49") (name "MEM03") (class "Default")
      (node (ref "E12") (pin "12") (pinfunction "Y4_12") (pintype "tri_state"))
      (node (ref "H04") (pin "M2") (pinfunction "1_M2") (pintype "bidirectional"))
    )
    (net (code "50") (name "MEM04") (class "Default")
      (node (ref "E12") (pin "9") (pinfunction "Y1_9") (pintype "tri_state"))
      (node (ref "H04") (pin "P2") (pinfunction "1_P2") (pintype "bidirectional"))
    )
    (net (code "51") (name "MEM05") (class "Default")
      (node (ref "E12") (pin "7") (pinfunction "Y2_7") (pintype "tri_state"))
      (node (ref "H04") (pin "S2") (pinfunction "1_S2") (pintype "bidirectional"))
    )
    (net (code "52") (name "MEM06") (class "Default")
      (node (ref "E12") (pin "5") (pinfunction "Y3_5") (pintype "tri_state"))
      (node (ref "H04") (pin "T2") (pinfunction "1_T2") (pintype "bidirectional"))
    )
    (net (code "53") (name "MEM07") (class "Default")
      (node (ref "E12") (pin "3") (pinfunction "Y4_3") (pintype "tri_state"))
      (node (ref "H04") (pin "V2") (pinfunction "1_V2") (pintype "bidirectional"))
    )
    (net (code "54") (name "MEM08") (class "Default")
      (node (ref "E13") (pin "18") (pinfunction "Y1_18") (pintype "tri_state"))
      (node (ref "H05") (pin "D2") (pinfunction "1_D2") (pintype "bidirectional"))
      (node (ref "SV4") (pin "41") (pinfunction "41_41") (pintype "passive"))
      (node (ref "SV5") (pin "41") (pinfunction "41_41") (pintype "passive"))
    )
    (net (code "55") (name "MEM09") (class "Default")
      (node (ref "E13") (pin "16") (pinfunction "Y2_16") (pintype "tri_state"))
      (node (ref "H05") (pin "E2") (pinfunction "1_E2") (pintype "bidirectional"))
      (node (ref "SV4") (pin "39") (pinfunction "39_39") (pintype "passive"))
      (node (ref "SV5") (pin "39") (pinfunction "39_39") (pintype "passive"))
    )
    (net (code "56") (name "MEM10") (class "Default")
      (node (ref "E13") (pin "14") (pinfunction "Y3_14") (pintype "tri_state"))
      (node (ref "H05") (pin "H2") (pinfunction "1_H2") (pintype "bidirectional"))
      (node (ref "SV4") (pin "40") (pinfunction "40_40") (pintype "passive"))
      (node (ref "SV5") (pin "40") (pinfunction "40_40") (pintype "passive"))
    )
    (net (code "57") (name "MEM11") (class "Default")
      (node (ref "E13") (pin "12") (pinfunction "Y4_12") (pintype "tri_state"))
      (node (ref "H05") (pin "K2") (pinfunction "1_K2") (pintype "bidirectional"))
      (node (ref "SV4") (pin "37") (pinfunction "37_37") (pintype "passive"))
      (node (ref "SV5") (pin "37") (pinfunction "37_37") (pintype "passive"))
    )
    (net (code "58") (name "MEMDONE(0)") (class "Default")
      (node (ref "E5") (pin "1") (pinfunction "O_1") (pintype "open_collector"))
      (node (ref "H05") (pin "S2") (pinfunction "1_S2") (pintype "bidirectional"))
    )
    (net (code "59") (name "MEMDONE(1)") (class "Default")
      (node (ref "E5") (pin "2") (pinfunction "I0_2") (pintype "input"))
      (node (ref "E5") (pin "3") (pinfunction "I1_3") (pintype "input"))
      (node (ref "E9") (pin "5") (pinfunction "Q_5") (pintype "output"))
    )
    (net (code "60") (name "MEMSTART(0)") (class "Default")
      (node (ref "E1") (pin "6") (pinfunction "O_6") (pintype "output"))
      (node (ref "E4") (pin "1") (pinfunction "IN_1") (pintype "input"))
      (node (ref "RESET") (pin "3") (pinfunction "3_3") (pintype "passive"))
    )
    (net (code "61") (name "MEMSTART(1)") (class "Default")
      (node (ref "E1") (pin "5") (pinfunction "I1_5") (pintype "input"))
      (node (ref "H05") (pin "M2") (pinfunction "1_M2") (pintype "bidirectional"))
      (node (ref "R1") (pin "1") (pinfunction "1_1") (pintype "passive"))
    )
    (net (code "62") (name "MEM_P") (class "Default")
      (node (ref "E13") (pin "9") (pinfunction "Y1_9") (pintype "tri_state"))
      (node (ref "H04") (pin "D2") (pinfunction "1_D2") (pintype "bidirectional"))
    )
    (net (code "63") (name "MS100") (class "Default")
      (node (ref "E1") (pin "12") (pinfunction "I0_12") (pintype "input"))
      (node (ref "E1") (pin "13") (pinfunction "I1_13") (pintype "input"))
      (node (ref "E4") (pin "2") (pinfunction "TAP2_2") (pintype "output"))
    )
    (net (code "64") (name "MS150") (class "Default")
      (node (ref "E11") (pin "4") (pinfunction "PRE_4") (pintype "input"))
      (node (ref "E4") (pin "6") (pinfunction "TAP3_6") (pintype "output"))
    )
    (net (code "65") (name "MS250") (class "Default")
      (node (ref "E3") (pin "1") (pinfunction "IN_1") (pintype "input"))
      (node (ref "E4") (pin "5") (pinfunction "TAP5_5") (pintype "output"))
    )
    (net (code "66") (name "MS350") (class "Default")
      (node (ref "E10") (pin "4") (pinfunction "PRE_4") (pintype "input"))
      (node (ref "E3") (pin "2") (pinfunction "TAP2_2") (pintype "output"))
    )
    (net (code "67") (name "MS400") (class "Default")
      (node (ref "E10") (pin "1") (pinfunction "CLR_1") (pintype "input"))
      (node (ref "E3") (pin "6") (pinfunction "TAP3_6") (pintype "output"))
    )
    (net (code "68") (name "MS500") (class "Default")
      (node (ref "E2") (pin "1") (pinfunction "IN_1") (pintype "input"))
      (node (ref "E3") (pin "5") (pinfunction "TAP5_5") (pintype "output"))
    )
    (net (code "69") (name "MS650") (class "Default")
      (node (ref "E11") (pin "1") (pinfunction "CLR_1") (pintype "input"))
      (node (ref "E2") (pin "6") (pinfunction "TAP3_6") (pintype "output"))
    )
    (net (code "70") (name "NS100") (class "Default")
      (node (ref "E1") (pin "11") (pinfunction "O_11") (pintype "output"))
      (node (ref "E11") (pin "11") (pinfunction "CLK_11") (pintype "input"))
    )
    (net (code "71") (name "Net-(E1C-I0)") (class "Default")
      (node (ref "E1") (pin "10") (pinfunction "I1_10") (pintype "input"))
      (node (ref "E1") (pin "9") (pinfunction "I0_9") (pintype "input"))
      (node (ref "RESET") (pin "2") (pinfunction "2_2") (pintype "passive"))
    )
    (net (code "72") (name "Net-(E5D-I0)") (class "Default")
      (node (ref "C1") (pin "1") (pinfunction "1_1") (pintype "passive"))
      (node (ref "D1") (pin "A") (pinfunction "A_A") (pintype "passive"))
      (node (ref "E5") (pin "11") (pinfunction "I0_11") (pintype "input"))
      (node (ref "E5") (pin "12") (pinfunction "I1_12") (pintype "input"))
      (node (ref "R3") (pin "1") (pinfunction "1_1") (pintype "passive"))
    )
    (net (code "73") (name "Net-(E18A-I0)") (class "Default")
      (node (ref "E18") (pin "1") (pinfunction "I0_1") (pintype "input"))
      (node (ref "FIELDS") (pin "2") (pinfunction "2_2") (pintype "passive"))
    )
    (net (code "74") (name "Net-(E18A-I1)") (class "Default")
      (node (ref "E18") (pin "2") (pinfunction "I1_2") (pintype "input"))
      (node (ref "FIELDS") (pin "4") (pinfunction "4_4") (pintype "passive"))
    )
    (net (code "75") (name "Net-(E18A-I2)") (class "Default")
      (node (ref "E18") (pin "3") (pinfunction "I2_3") (pintype "input"))
      (node (ref "FIELDS") (pin "6") (pinfunction "6_6") (pintype "passive"))
    )
    (net (code "76") (name "Net-(E18A-I3)") (class "Default")
      (node (ref "E18") (pin "4") (pinfunction "I3_4") (pintype "input"))
      (node (ref "FIELDS") (pin "8") (pinfunction "8_8") (pintype "passive"))
    )
    (net (code "77") (name "Net-(E18A-I4)") (class "Default")
      (node (ref "E18") (pin "5") (pinfunction "I4_5") (pintype "input"))
      (node (ref "FIELDS") (pin "10") (pinfunction "10_10") (pintype "passive"))
    )
    (net (code "78") (name "Net-(E18A-I5)") (class "Default")
      (node (ref "E18") (pin "6") (pinfunction "I5_6") (pintype "input"))
      (node (ref "FIELDS") (pin "12") (pinfunction "12_12") (pintype "passive"))
    )
    (net (code "79") (name "Net-(E18A-I6)") (class "Default")
      (node (ref "E18") (pin "11") (pinfunction "I6_11") (pintype "input"))
      (node (ref "FIELDS") (pin "16") (pinfunction "16_16") (pintype "passive"))
    )
    (net (code "80") (name "Net-(E18A-I7)") (class "Default")
      (node (ref "E18") (pin "12") (pinfunction "I7_12") (pintype "input"))
      (node (ref "FIELDS") (pin "14") (pinfunction "14_14") (pintype "passive"))
    )
    (net (code "81") (name "Net-(E19A-Y0)") (class "Default")
      (node (ref "E19") (pin "15") (pinfunction "Y0_15") (pintype "output"))
      (node (ref "FIELDS") (pin "1") (pinfunction "1_1") (pintype "passive"))
    )
    (net (code "82") (name "Net-(E19A-Y1)") (class "Default")
      (node (ref "E19") (pin "14") (pinfunction "Y1_14") (pintype "output"))
      (node (ref "FIELDS") (pin "3") (pinfunction "3_3") (pintype "passive"))
    )
    (net (code "83") (name "Net-(E19A-Y2)") (class "Default")
      (node (ref "E19") (pin "13") (pinfunction "Y2_13") (pintype "output"))
      (node (ref "FIELDS") (pin "5") (pinfunction "5_5") (pintype "passive"))
    )
    (net (code "84") (name "Net-(E19A-Y3)") (class "Default")
      (node (ref "E19") (pin "12") (pinfunction "Y3_12") (pintype "output"))
      (node (ref "FIELDS") (pin "7") (pinfunction "7_7") (pintype "passive"))
    )
    (net (code "85") (name "Net-(E19A-Y4)") (class "Default")
      (node (ref "E19") (pin "11") (pinfunction "Y4_11") (pintype "output"))
      (node (ref "FIELDS") (pin "9") (pinfunction "9_9") (pintype "passive"))
    )
    (net (code "86") (name "Net-(E19A-Y5)") (class "Default")
      (node (ref "E19") (pin "10") (pinfunction "Y5_10") (pintype "output"))
      (node (ref "FIELDS") (pin "11") (pinfunction "11_11") (pintype "passive"))
    )
    (net (code "87") (name "Net-(E19A-Y6)") (class "Default")
      (node (ref "E19") (pin "9") (pinfunction "Y6_9") (pintype "output"))
      (node (ref "FIELDS") (pin "13") (pinfunction "13_13") (pintype "passive"))
    )
    (net (code "88") (name "Net-(E19A-Y7)") (class "Default")
      (node (ref "E19") (pin "7") (pinfunction "Y7_7") (pintype "output"))
      (node (ref "FIELDS") (pin "15") (pinfunction "15_15") (pintype "passive"))
    )
    (net (code "89") (name "OE(0)") (class "Default")
      (node (ref "E11") (pin "6") (pinfunction "~{Q}_6") (pintype "output"))
      (node (ref "E12") (pin "1") (pinfunction "G_1") (pintype "input"))
      (node (ref "E12") (pin "19") (pinfunction "G_19") (pintype "input"))
      (node (ref "E13") (pin "1") (pinfunction "G_1") (pintype "input"))
      (node (ref "E13") (pin "19") (pinfunction "G_19") (pintype "input"))
      (node (ref "E16") (pin "22") (pinfunction "~{OE}_22") (pintype "input"))
      (node (ref "E17") (pin "22") (pinfunction "~{OE}_22") (pintype "input"))
      (node (ref "SV2") (pin "22") (pinfunction "22_22") (pintype "passive"))
      (node (ref "SV4") (pin "22") (pinfunction "22_22") (pintype "passive"))
      (node (ref "SV5") (pin "22") (pinfunction "22_22") (pintype "passive"))
    )
    (net (code "90") (name "PARITY") (class "Default")
      (node (ref "E13") (pin "11") (pinfunction "A1_11") (pintype "input"))
      (node (ref "E13") (pin "13") (pinfunction "A2_13") (pintype "input"))
      (node (ref "E13") (pin "15") (pinfunction "A3_15") (pintype "input"))
      (node (ref "E13") (pin "17") (pinfunction "A4_17") (pintype "input"))
      (node (ref "E15") (pin "9") (pinfunction "Y1_9") (pintype "tri_state"))
      (node (ref "E16") (pin "16") (pinfunction "I/O4_16") (pintype "bidirectional"))
      (node (ref "SV2") (pin "3") (pinfunction "3_3") (pintype "passive"))
      (node (ref "SV3") (pin "3") (pinfunction "3_3") (pintype "passive"))
      (node (ref "SV4") (pin "3") (pinfunction "3_3") (pintype "passive"))
    )
    (net (code "91") (name "PWR_OK(0)") (class "Default")
      (node (ref "E5") (pin "13") (pinfunction "O_13") (pintype "open_collector"))
      (node (ref "R5") (pin "1") (pinfunction "1_1") (pintype "passive"))
      (node (ref "RESET") (pin "1") (pinfunction "1_1") (pintype "passive"))
    )
    (net (code "92") (name "RESET") (class "Default")
      (node (ref "E1") (pin "8") (pinfunction "O_8") (pintype "output"))
      (node (ref "E10") (pin "11") (pinfunction "CLK_11") (pintype "input"))
      (node (ref "E10") (pin "3") (pinfunction "CLK_3") (pintype "input"))
      (node (ref "E11") (pin "3") (pinfunction "CLK_3") (pintype "input"))
      (node (ref "E9") (pin "3") (pinfunction "CLK_3") (pintype "input"))
    )
    (net (code "93") (name "STROBE(0)") (class "Default")
      (node (ref "E5") (pin "4") (pinfunction "O_4") (pintype "open_collector"))
      (node (ref "H05") (pin "P2") (pinfunction "1_P2") (pintype "bidirectional"))
    )
    (net (code "94") (name "STROBE(1)") (class "Default")
      (node (ref "E10") (pin "5") (pinfunction "Q_5") (pintype "output"))
      (node (ref "E5") (pin "5") (pinfunction "I0_5") (pintype "input"))
      (node (ref "E5") (pin "6") (pinfunction "I1_6") (pintype "input"))
    )
    (net (code "95") (name "TP150") (class "Default")
      (node (ref "E10") (pin "10") (pinfunction "PRE_10") (pintype "input"))
      (node (ref "E8") (pin "6") (pinfunction "TAP3_6") (pintype "output"))
    )
    (net (code "96") (name "TP250") (class "Default")
      (node (ref "E7") (pin "1") (pinfunction "IN_1") (pintype "input"))
      (node (ref "E8") (pin "5") (pinfunction "TAP5_5") (pintype "output"))
    )
    (net (code "97") (name "TP300") (class "Default")
      (node (ref "E10") (pin "13") (pinfunction "CLR_13") (pintype "input"))
      (node (ref "E7") (pin "7") (pinfunction "TAP1_7") (pintype "output"))
    )
    (net (code "98") (name "TP500") (class "Default")
      (node (ref "E11") (pin "13") (pinfunction "CLR_13") (pintype "input"))
      (node (ref "E6") (pin "1") (pinfunction "IN_1") (pintype "input"))
      (node (ref "E7") (pin "5") (pinfunction "TAP5_5") (pintype "output"))
      (node (ref "E9") (pin "4") (pinfunction "PRE_4") (pintype "input"))
    )
    (net (code "99") (name "TP550") (class "Default")
      (node (ref "E6") (pin "7") (pinfunction "TAP1_7") (pintype "output"))
      (node (ref "E9") (pin "1") (pinfunction "CLR_1") (pintype "input"))
    )
    (net (code "100") (name "VCC") (class "Default")
      (node (ref "C10") (pin "1") (pinfunction "1_1") (pintype "passive"))
      (node (ref "C11") (pin "1") (pinfunction "1_1") (pintype "passive"))
      (node (ref "C12") (pin "1") (pinfunction "1_1") (pintype "passive"))
      (node (ref "C13") (pin "1") (pinfunction "1_1") (pintype "passive"))
      (node (ref "C14") (pin "1") (pinfunction "1_1") (pintype "passive"))
      (node (ref "C15") (pin "1") (pinfunction "1_1") (pintype "passive"))
      (node (ref "C16") (pin "1") (pinfunction "1_1") (pintype "passive"))
      (node (ref "C2") (pin "1") (pinfunction "1_1") (pintype "passive"))
      (node (ref "C3") (pin "1") (pinfunction "1_1") (pintype "passive"))
      (node (ref "C4") (pin "1") (pinfunction "1_1") (pintype "passive"))
      (node (ref "C5") (pin "1") (pinfunction "1_1") (pintype "passive"))
      (node (ref "C6") (pin "1") (pinfunction "1_1") (pintype "passive"))
      (node (ref "C7") (pin "1") (pinfunction "1_1") (pintype "passive"))
      (node (ref "C8") (pin "1") (pinfunction "1_1") (pintype "passive"))
      (node (ref "C9") (pin "1") (pinfunction "1_1") (pintype "passive"))
      (node (ref "D1") (pin "C") (pinfunction "C_C") (pintype "passive"))
      (node (ref "E11") (pin "10") (pinfunction "PRE_10") (pintype "input"))
      (node (ref "E16") (pin "28") (pinfunction "VCC_28") (pintype "power_in"))
      (node (ref "E17") (pin "28") (pinfunction "VCC_28") (pintype "power_in"))
      (node (ref "E19") (pin "6") (pinfunction "G1_6") (pintype "input"))
      (node (ref "E5") (pin "8") (pinfunction "I0_8") (pintype "input"))
      (node (ref "E5") (pin "9") (pinfunction "I1_9") (pintype "input"))
      (node (ref "E9") (pin "10") (pinfunction "PRE_10") (pintype "input"))
      (node (ref "E9") (pin "11") (pinfunction "CLK_11") (pintype "input"))
      (node (ref "E9") (pin "12") (pinfunction "D_12") (pintype "input"))
      (node (ref "E9") (pin "13") (pinfunction "CLR_13") (pintype "input"))
      (node (ref "R3") (pin "2") (pinfunction "2_2") (pintype "passive"))
      (node (ref "R5") (pin "2") (pinfunction "2_2") (pintype "passive"))
      (node (ref "SV1") (pin "49") (pinfunction "49_49") (pintype "passive"))
      (node (ref "SV1") (pin "50") (pinfunction "50_50") (pintype "passive"))
      (node (ref "SV2") (pin "49") (pinfunction "49_49") (pintype "passive"))
      (node (ref "SV2") (pin "50") (pinfunction "50_50") (pintype "passive"))
      (node (ref "SV3") (pin "49") (pinfunction "49_49") (pintype "passive"))
      (node (ref "SV3") (pin "50") (pinfunction "50_50") (pintype "passive"))
      (node (ref "SV4") (pin "49") (pinfunction "49_49") (pintype "passive"))
      (node (ref "SV4") (pin "50") (pinfunction "50_50") (pintype "passive"))
      (node (ref "SV5") (pin "49") (pinfunction "49_49") (pintype "passive"))
      (node (ref "SV5") (pin "50") (pinfunction "50_50") (pintype "passive"))
      (node (ref "X1") (pin "1") (pinfunction "KL_1") (pintype "passive"))
    )
    (net (code "101") (name "WE(0)") (class "Default")
      (node (ref "E10") (pin "8") (pinfunction "~{Q}_8") (pintype "output"))
      (node (ref "E14") (pin "1") (pinfunction "G_1") (pintype "input"))
      (node (ref "E14") (pin "19") (pinfunction "G_19") (pintype "input"))
      (node (ref "E15") (pin "1") (pinfunction "G_1") (pintype "input"))
      (node (ref "E15") (pin "19") (pinfunction "G_19") (pintype "input"))
      (node (ref "E16") (pin "27") (pinfunction "~{WE}_27") (pintype "input"))
      (node (ref "E17") (pin "27") (pinfunction "~{WE}_27") (pintype "input"))
      (node (ref "SV2") (pin "32") (pinfunction "32_32") (pintype "passive"))
      (node (ref "SV3") (pin "32") (pinfunction "32_32") (pintype "passive"))
      (node (ref "SV5") (pin "32") (pinfunction "32_32") (pintype "passive"))
    )
    (net (code "102") (name "unconnected-(E2A-TAP1-Pad7)") (class "Default")
      (node (ref "E2") (pin "7") (pinfunction "TAP1_7") (pintype "output"))
    )
    (net (code "103") (name "unconnected-(E2A-TAP2-Pad2)") (class "Default")
      (node (ref "E2") (pin "2") (pinfunction "TAP2_2") (pintype "output"))
    )
    (net (code "104") (name "unconnected-(E2A-TAP4-Pad3)") (class "Default")
      (node (ref "E2") (pin "3") (pinfunction "TAP4_3") (pintype "output"))
    )
    (net (code "105") (name "unconnected-(E2A-TAP5-Pad5)") (class "Default")
      (node (ref "E2") (pin "5") (pinfunction "TAP5_5") (pintype "output"))
    )
    (net (code "106") (name "unconnected-(E3A-TAP1-Pad7)") (class "Default")
      (node (ref "E3") (pin "7") (pinfunction "TAP1_7") (pintype "output"))
    )
    (net (code "107") (name "unconnected-(E3A-TAP4-Pad3)") (class "Default")
      (node (ref "E3") (pin "3") (pinfunction "TAP4_3") (pintype "output"))
    )
    (net (code "108") (name "unconnected-(E4A-TAP1-Pad7)") (class "Default")
      (node (ref "E4") (pin "7") (pinfunction "TAP1_7") (pintype "output"))
    )
    (net (code "109") (name "unconnected-(E4A-TAP4-Pad3)") (class "Default")
      (node (ref "E4") (pin "3") (pinfunction "TAP4_3") (pintype "output"))
    )
    (net (code "110") (name "unconnected-(E5C-O-Pad10)") (class "Default")
      (node (ref "E5") (pin "10") (pinfunction "O_10") (pintype "open_collector"))
    )
    (net (code "111") (name "unconnected-(E6A-TAP2-Pad2)") (class "Default")
      (node (ref "E6") (pin "2") (pinfunction "TAP2_2") (pintype "output"))
    )
    (net (code "112") (name "unconnected-(E6A-TAP3-Pad6)") (class "Default")
      (node (ref "E6") (pin "6") (pinfunction "TAP3_6") (pintype "output"))
    )
    (net (code "113") (name "unconnected-(E6A-TAP4-Pad3)") (class "Default")
      (node (ref "E6") (pin "3") (pinfunction "TAP4_3") (pintype "output"))
    )
    (net (code "114") (name "unconnected-(E6A-TAP5-Pad5)") (class "Default")
      (node (ref "E6") (pin "5") (pinfunction "TAP5_5") (pintype "output"))
    )
    (net (code "115") (name "unconnected-(E7A-TAP2-Pad2)") (class "Default")
      (node (ref "E7") (pin "2") (pinfunction "TAP2_2") (pintype "output"))
    )
    (net (code "116") (name "unconnected-(E7A-TAP3-Pad6)") (class "Default")
      (node (ref "E7") (pin "6") (pinfunction "TAP3_6") (pintype "output"))
    )
    (net (code "117") (name "unconnected-(E7A-TAP4-Pad3)") (class "Default")
      (node (ref "E7") (pin "3") (pinfunction "TAP4_3") (pintype "output"))
    )
    (net (code "118") (name "unconnected-(E8A-TAP1-Pad7)") (class "Default")
      (node (ref "E8") (pin "7") (pinfunction "TAP1_7") (pintype "output"))
    )
    (net (code "119") (name "unconnected-(E8A-TAP2-Pad2)") (class "Default")
      (node (ref "E8") (pin "2") (pinfunction "TAP2_2") (pintype "output"))
    )
    (net (code "120") (name "unconnected-(E8A-TAP4-Pad3)") (class "Default")
      (node (ref "E8") (pin "3") (pinfunction "TAP4_3") (pintype "output"))
    )
    (net (code "121") (name "unconnected-(E9A-~{Q}-Pad6)") (class "Default")
      (node (ref "E9") (pin "6") (pinfunction "~{Q}_6") (pintype "output"))
    )
    (net (code "122") (name "unconnected-(E9B-Q-Pad9)") (class "Default")
      (node (ref "E9") (pin "9") (pinfunction "Q_9") (pintype "output"))
    )
    (net (code "123") (name "unconnected-(E9B-~{Q}-Pad8)") (class "Default")
      (node (ref "E9") (pin "8") (pinfunction "~{Q}_8") (pintype "output"))
    )
    (net (code "124") (name "unconnected-(E10A-~{Q}-Pad6)") (class "Default")
      (node (ref "E10") (pin "6") (pinfunction "~{Q}_6") (pintype "output"))
    )
    (net (code "125") (name "unconnected-(E10B-Q-Pad9)") (class "Default")
      (node (ref "E10") (pin "9") (pinfunction "Q_9") (pintype "output"))
    )
    (net (code "126") (name "unconnected-(E11A-Q-Pad5)") (class "Default")
      (node (ref "E11") (pin "5") (pinfunction "Q_5") (pintype "output"))
    )
    (net (code "127") (name "unconnected-(E11B-Q-Pad9)") (class "Default")
      (node (ref "E11") (pin "9") (pinfunction "Q_9") (pintype "output"))
    )
    (net (code "128") (name "unconnected-(E13B-Y2-Pad7)") (class "Default")
      (node (ref "E13") (pin "7") (pinfunction "Y2_7") (pintype "tri_state"))
    )
    (net (code "129") (name "unconnected-(E13B-Y3-Pad5)") (class "Default")
      (node (ref "E13") (pin "5") (pinfunction "Y3_5") (pintype "tri_state"))
    )
    (net (code "130") (name "unconnected-(E13B-Y4-Pad3)") (class "Default")
      (node (ref "E13") (pin "3") (pinfunction "Y4_3") (pintype "tri_state"))
    )
    (net (code "131") (name "unconnected-(E15B-Y2-Pad7)") (class "Default")
      (node (ref "E15") (pin "7") (pinfunction "Y2_7") (pintype "tri_state"))
    )
    (net (code "132") (name "unconnected-(E15B-Y3-Pad5)") (class "Default")
      (node (ref "E15") (pin "5") (pinfunction "Y3_5") (pintype "tri_state"))
    )
    (net (code "133") (name "unconnected-(E15B-Y4-Pad3)") (class "Default")
      (node (ref "E15") (pin "3") (pinfunction "Y4_3") (pintype "tri_state"))
    )
    (net (code "134") (name "unconnected-(E16-I{slash}O5-Pad17)") (class "Default")
      (node (ref "E16") (pin "17") (pinfunction "I/O5_17") (pintype "bidirectional"))
    )
    (net (code "135") (name "unconnected-(E16-I{slash}O6-Pad18)") (class "Default")
      (node (ref "E16") (pin "18") (pinfunction "I/O6_18") (pintype "bidirectional"))
    )
    (net (code "136") (name "unconnected-(E16-I{slash}O7-Pad19)") (class "Default")
      (node (ref "E16") (pin "19") (pinfunction "I/O7_19") (pintype "bidirectional"))
    )
    (net (code "137") (name "unconnected-(SV1-Pad3)") (class "Default")
      (node (ref "SV1") (pin "3") (pinfunction "3_3") (pintype "passive"))
    )
    (net (code "138") (name "unconnected-(SV1-Pad4)") (class "Default")
      (node (ref "SV1") (pin "4") (pinfunction "4_4") (pintype "passive"))
    )
    (net (code "139") (name "unconnected-(SV1-Pad5)") (class "Default")
      (node (ref "SV1") (pin "5") (pinfunction "5_5") (pintype "passive"))
    )
    (net (code "140") (name "unconnected-(SV1-Pad6)") (class "Default")
      (node (ref "SV1") (pin "6") (pinfunction "6_6") (pintype "passive"))
    )
    (net (code "141") (name "unconnected-(SV1-Pad7)") (class "Default")
      (node (ref "SV1") (pin "7") (pinfunction "7_7") (pintype "passive"))
    )
    (net (code "142") (name "unconnected-(SV1-Pad8)") (class "Default")
      (node (ref "SV1") (pin "8") (pinfunction "8_8") (pintype "passive"))
    )
    (net (code "143") (name "unconnected-(SV1-Pad9)") (class "Default")
      (node (ref "SV1") (pin "9") (pinfunction "9_9") (pintype "passive"))
    )
    (net (code "144") (name "unconnected-(SV1-Pad10)") (class "Default")
      (node (ref "SV1") (pin "10") (pinfunction "10_10") (pintype "passive"))
    )
    (net (code "145") (name "unconnected-(SV1-Pad11)") (class "Default")
      (node (ref "SV1") (pin "11") (pinfunction "11_11") (pintype "passive"))
    )
    (net (code "146") (name "unconnected-(SV1-Pad12)") (class "Default")
      (node (ref "SV1") (pin "12") (pinfunction "12_12") (pintype "passive"))
    )
    (net (code "147") (name "unconnected-(SV1-Pad13)") (class "Default")
      (node (ref "SV1") (pin "13") (pinfunction "13_13") (pintype "passive"))
    )
    (net (code "148") (name "unconnected-(SV1-Pad14)") (class "Default")
      (node (ref "SV1") (pin "14") (pinfunction "14_14") (pintype "passive"))
    )
    (net (code "149") (name "unconnected-(SV1-Pad15)") (class "Default")
      (node (ref "SV1") (pin "15") (pinfunction "15_15") (pintype "passive"))
    )
    (net (code "150") (name "unconnected-(SV1-Pad16)") (class "Default")
      (node (ref "SV1") (pin "16") (pinfunction "16_16") (pintype "passive"))
    )
    (net (code "151") (name "unconnected-(SV1-Pad17)") (class "Default")
      (node (ref "SV1") (pin "17") (pinfunction "17_17") (pintype "passive"))
    )
    (net (code "152") (name "unconnected-(SV1-Pad18)") (class "Default")
      (node (ref "SV1") (pin "18") (pinfunction "18_18") (pintype "passive"))
    )
    (net (code "153") (name "unconnected-(SV1-Pad19)") (class "Default")
      (node (ref "SV1") (pin "19") (pinfunction "19_19") (pintype "passive"))
    )
    (net (code "154") (name "unconnected-(SV1-Pad21)") (class "Default")
      (node (ref "SV1") (pin "21") (pinfunction "21_21") (pintype "passive"))
    )
    (net (code "155") (name "unconnected-(SV1-Pad22)") (class "Default")
      (node (ref "SV1") (pin "22") (pinfunction "22_22") (pintype "passive"))
    )
    (net (code "156") (name "unconnected-(SV1-Pad23)") (class "Default")
      (node (ref "SV1") (pin "23") (pinfunction "23_23") (pintype "passive"))
    )
    (net (code "157") (name "unconnected-(SV1-Pad25)") (class "Default")
      (node (ref "SV1") (pin "25") (pinfunction "25_25") (pintype "passive"))
    )
    (net (code "158") (name "unconnected-(SV1-Pad32)") (class "Default")
      (node (ref "SV1") (pin "32") (pinfunction "32_32") (pintype "passive"))
    )
    (net (code "159") (name "unconnected-(SV1-Pad35)") (class "Default")
      (node (ref "SV1") (pin "35") (pinfunction "35_35") (pintype "passive"))
    )
    (net (code "160") (name "unconnected-(SV1-Pad36)") (class "Default")
      (node (ref "SV1") (pin "36") (pinfunction "36_36") (pintype "passive"))
    )
    (net (code "161") (name "unconnected-(SV1-Pad37)") (class "Default")
      (node (ref "SV1") (pin "37") (pinfunction "37_37") (pintype "passive"))
    )
    (net (code "162") (name "unconnected-(SV1-Pad38)") (class "Default")
      (node (ref "SV1") (pin "38") (pinfunction "38_38") (pintype "passive"))
    )
    (net (code "163") (name "unconnected-(SV1-Pad39)") (class "Default")
      (node (ref "SV1") (pin "39") (pinfunction "39_39") (pintype "passive"))
    )
    (net (code "164") (name "unconnected-(SV1-Pad40)") (class "Default")
      (node (ref "SV1") (pin "40") (pinfunction "40_40") (pintype "passive"))
    )
    (net (code "165") (name "unconnected-(SV1-Pad41)") (class "Default")
      (node (ref "SV1") (pin "41") (pinfunction "41_41") (pintype "passive"))
    )
    (net (code "166") (name "unconnected-(SV1-Pad42)") (class "Default")
      (node (ref "SV1") (pin "42") (pinfunction "42_42") (pintype "passive"))
    )
    (net (code "167") (name "unconnected-(SV1-Pad45)") (class "Default")
      (node (ref "SV1") (pin "45") (pinfunction "45_45") (pintype "passive"))
    )
    (net (code "168") (name "unconnected-(SV1-Pad47)") (class "Default")
      (node (ref "SV1") (pin "47") (pinfunction "47_47") (pintype "passive"))
    )
    (net (code "169") (name "unconnected-(SV1-Pad48)") (class "Default")
      (node (ref "SV1") (pin "48") (pinfunction "48_48") (pintype "passive"))
    )
    (net (code "170") (name "unconnected-(SV2-Pad34)") (class "Default")
      (node (ref "SV2") (pin "34") (pinfunction "34_34") (pintype "passive"))
    )
    (net (code "171") (name "unconnected-(SV2-Pad37)") (class "Default")
      (node (ref "SV2") (pin "37") (pinfunction "37_37") (pintype "passive"))
    )
    (net (code "172") (name "unconnected-(SV2-Pad39)") (class "Default")
      (node (ref "SV2") (pin "39") (pinfunction "39_39") (pintype "passive"))
    )
    (net (code "173") (name "unconnected-(SV2-Pad40)") (class "Default")
      (node (ref "SV2") (pin "40") (pinfunction "40_40") (pintype "passive"))
    )
    (net (code "174") (name "unconnected-(SV2-Pad41)") (class "Default")
      (node (ref "SV2") (pin "41") (pinfunction "41_41") (pintype "passive"))
    )
    (net (code "175") (name "unconnected-(SV2-Pad42)") (class "Default")
      (node (ref "SV2") (pin "42") (pinfunction "42_42") (pintype "passive"))
    )
    (net (code "176") (name "unconnected-(SV2-Pad43)") (class "Default")
      (node (ref "SV2") (pin "43") (pinfunction "43_43") (pintype "passive"))
    )
    (net (code "177") (name "unconnected-(SV2-Pad44)") (class "Default")
      (node (ref "SV2") (pin "44") (pinfunction "44_44") (pintype "passive"))
    )
    (net (code "178") (name "unconnected-(SV2-Pad45)") (class "Default")
      (node (ref "SV2") (pin "45") (pinfunction "45_45") (pintype "passive"))
    )
    (net (code "179") (name "unconnected-(SV2-Pad46)") (class "Default")
      (node (ref "SV2") (pin "46") (pinfunction "46_46") (pintype "passive"))
    )
    (net (code "180") (name "unconnected-(SV2-Pad47)") (class "Default")
      (node (ref "SV2") (pin "47") (pinfunction "47_47") (pintype "passive"))
    )
    (net (code "181") (name "unconnected-(SV2-Pad48)") (class "Default")
      (node (ref "SV2") (pin "48") (pinfunction "48_48") (pintype "passive"))
    )
    (net (code "182") (name "unconnected-(SV3-Pad15)") (class "Default")
      (node (ref "SV3") (pin "15") (pinfunction "15_15") (pintype "passive"))
    )
    (net (code "183") (name "unconnected-(SV3-Pad17)") (class "Default")
      (node (ref "SV3") (pin "17") (pinfunction "17_17") (pintype "passive"))
    )
    (net (code "184") (name "unconnected-(SV3-Pad18)") (class "Default")
      (node (ref "SV3") (pin "18") (pinfunction "18_18") (pintype "passive"))
    )
    (net (code "185") (name "unconnected-(SV3-Pad19)") (class "Default")
      (node (ref "SV3") (pin "19") (pinfunction "19_19") (pintype "passive"))
    )
    (net (code "186") (name "unconnected-(SV3-Pad20)") (class "Default")
      (node (ref "SV3") (pin "20") (pinfunction "20_20") (pintype "passive"))
    )
    (net (code "187") (name "unconnected-(SV3-Pad21)") (class "Default")
      (node (ref "SV3") (pin "21") (pinfunction "21_21") (pintype "passive"))
    )
    (net (code "188") (name "unconnected-(SV3-Pad22)") (class "Default")
      (node (ref "SV3") (pin "22") (pinfunction "22_22") (pintype "passive"))
    )
    (net (code "189") (name "unconnected-(SV3-Pad23)") (class "Default")
      (node (ref "SV3") (pin "23") (pinfunction "23_23") (pintype "passive"))
    )
    (net (code "190") (name "unconnected-(SV3-Pad24)") (class "Default")
      (node (ref "SV3") (pin "24") (pinfunction "24_24") (pintype "passive"))
    )
    (net (code "191") (name "unconnected-(SV3-Pad25)") (class "Default")
      (node (ref "SV3") (pin "25") (pinfunction "25_25") (pintype "passive"))
    )
    (net (code "192") (name "unconnected-(SV3-Pad26)") (class "Default")
      (node (ref "SV3") (pin "26") (pinfunction "26_26") (pintype "passive"))
    )
    (net (code "193") (name "unconnected-(SV3-Pad27)") (class "Default")
      (node (ref "SV3") (pin "27") (pinfunction "27_27") (pintype "passive"))
    )
    (net (code "194") (name "unconnected-(SV3-Pad28)") (class "Default")
      (node (ref "SV3") (pin "28") (pinfunction "28_28") (pintype "passive"))
    )
    (net (code "195") (name "unconnected-(SV3-Pad29)") (class "Default")
      (node (ref "SV3") (pin "29") (pinfunction "29_29") (pintype "passive"))
    )
    (net (code "196") (name "unconnected-(SV3-Pad34)") (class "Default")
      (node (ref "SV3") (pin "34") (pinfunction "34_34") (pintype "passive"))
    )
    (net (code "197") (name "unconnected-(SV3-Pad37)") (class "Default")
      (node (ref "SV3") (pin "37") (pinfunction "37_37") (pintype "passive"))
    )
    (net (code "198") (name "unconnected-(SV3-Pad39)") (class "Default")
      (node (ref "SV3") (pin "39") (pinfunction "39_39") (pintype "passive"))
    )
    (net (code "199") (name "unconnected-(SV3-Pad40)") (class "Default")
      (node (ref "SV3") (pin "40") (pinfunction "40_40") (pintype "passive"))
    )
    (net (code "200") (name "unconnected-(SV3-Pad41)") (class "Default")
      (node (ref "SV3") (pin "41") (pinfunction "41_41") (pintype "passive"))
    )
    (net (code "201") (name "unconnected-(SV3-Pad45)") (class "Default")
      (node (ref "SV3") (pin "45") (pinfunction "45_45") (pintype "passive"))
    )
    (net (code "202") (name "unconnected-(SV3-Pad47)") (class "Default")
      (node (ref "SV3") (pin "47") (pinfunction "47_47") (pintype "passive"))
    )
    (net (code "203") (name "unconnected-(SV3-Pad48)") (class "Default")
      (node (ref "SV3") (pin "48") (pinfunction "48_48") (pintype "passive"))
    )
    (net (code "204") (name "unconnected-(SV4-Pad15)") (class "Default")
      (node (ref "SV4") (pin "15") (pinfunction "15_15") (pintype "passive"))
    )
    (net (code "205") (name "unconnected-(SV4-Pad17)") (class "Default")
      (node (ref "SV4") (pin "17") (pinfunction "17_17") (pintype "passive"))
    )
    (net (code "206") (name "unconnected-(SV4-Pad18)") (class "Default")
      (node (ref "SV4") (pin "18") (pinfunction "18_18") (pintype "passive"))
    )
    (net (code "207") (name "unconnected-(SV4-Pad19)") (class "Default")
      (node (ref "SV4") (pin "19") (pinfunction "19_19") (pintype "passive"))
    )
    (net (code "208") (name "unconnected-(SV4-Pad20)") (class "Default")
      (node (ref "SV4") (pin "20") (pinfunction "20_20") (pintype "passive"))
    )
    (net (code "209") (name "unconnected-(SV4-Pad21)") (class "Default")
      (node (ref "SV4") (pin "21") (pinfunction "21_21") (pintype "passive"))
    )
    (net (code "210") (name "unconnected-(SV4-Pad23)") (class "Default")
      (node (ref "SV4") (pin "23") (pinfunction "23_23") (pintype "passive"))
    )
    (net (code "211") (name "unconnected-(SV4-Pad24)") (class "Default")
      (node (ref "SV4") (pin "24") (pinfunction "24_24") (pintype "passive"))
    )
    (net (code "212") (name "unconnected-(SV4-Pad25)") (class "Default")
      (node (ref "SV4") (pin "25") (pinfunction "25_25") (pintype "passive"))
    )
    (net (code "213") (name "unconnected-(SV4-Pad26)") (class "Default")
      (node (ref "SV4") (pin "26") (pinfunction "26_26") (pintype "passive"))
    )
    (net (code "214") (name "unconnected-(SV4-Pad27)") (class "Default")
      (node (ref "SV4") (pin "27") (pinfunction "27_27") (pintype "passive"))
    )
    (net (code "215") (name "unconnected-(SV4-Pad28)") (class "Default")
      (node (ref "SV4") (pin "28") (pinfunction "28_28") (pintype "passive"))
    )
    (net (code "216") (name "unconnected-(SV4-Pad29)") (class "Default")
      (node (ref "SV4") (pin "29") (pinfunction "29_29") (pintype "passive"))
    )
    (net (code "217") (name "unconnected-(SV4-Pad30)") (class "Default")
      (node (ref "SV4") (pin "30") (pinfunction "30_30") (pintype "passive"))
    )
    (net (code "218") (name "unconnected-(SV4-Pad31)") (class "Default")
      (node (ref "SV4") (pin "31") (pinfunction "31_31") (pintype "passive"))
    )
    (net (code "219") (name "unconnected-(SV4-Pad32)") (class "Default")
      (node (ref "SV4") (pin "32") (pinfunction "32_32") (pintype "passive"))
    )
    (net (code "220") (name "unconnected-(SV4-Pad33)") (class "Default")
      (node (ref "SV4") (pin "33") (pinfunction "33_33") (pintype "passive"))
    )
    (net (code "221") (name "unconnected-(SV4-Pad34)") (class "Default")
      (node (ref "SV4") (pin "34") (pinfunction "34_34") (pintype "passive"))
    )
    (net (code "222") (name "unconnected-(SV4-Pad35)") (class "Default")
      (node (ref "SV4") (pin "35") (pinfunction "35_35") (pintype "passive"))
    )
    (net (code "223") (name "unconnected-(SV4-Pad36)") (class "Default")
      (node (ref "SV4") (pin "36") (pinfunction "36_36") (pintype "passive"))
    )
    (net (code "224") (name "unconnected-(SV4-Pad38)") (class "Default")
      (node (ref "SV4") (pin "38") (pinfunction "38_38") (pintype "passive"))
    )
    (net (code "225") (name "unconnected-(SV4-Pad42)") (class "Default")
      (node (ref "SV4") (pin "42") (pinfunction "42_42") (pintype "passive"))
    )
    (net (code "226") (name "unconnected-(SV4-Pad43)") (class "Default")
      (node (ref "SV4") (pin "43") (pinfunction "43_43") (pintype "passive"))
    )
    (net (code "227") (name "unconnected-(SV4-Pad44)") (class "Default")
      (node (ref "SV4") (pin "44") (pinfunction "44_44") (pintype "passive"))
    )
    (net (code "228") (name "unconnected-(SV4-Pad45)") (class "Default")
      (node (ref "SV4") (pin "45") (pinfunction "45_45") (pintype "passive"))
    )
    (net (code "229") (name "unconnected-(SV4-Pad46)") (class "Default")
      (node (ref "SV4") (pin "46") (pinfunction "46_46") (pintype "passive"))
    )
    (net (code "230") (name "unconnected-(SV4-Pad47)") (class "Default")
      (node (ref "SV4") (pin "47") (pinfunction "47_47") (pintype "passive"))
    )
    (net (code "231") (name "unconnected-(SV4-Pad48)") (class "Default")
      (node (ref "SV4") (pin "48") (pinfunction "48_48") (pintype "passive"))
    )
    (net (code "232") (name "unconnected-(SV5-Pad3)") (class "Default")
      (node (ref "SV5") (pin "3") (pinfunction "3_3") (pintype "passive"))
    )
    (net (code "233") (name "unconnected-(SV5-Pad4)") (class "Default")
      (node (ref "SV5") (pin "4") (pinfunction "4_4") (pintype "passive"))
    )
    (net (code "234") (name "unconnected-(SV5-Pad5)") (class "Default")
      (node (ref "SV5") (pin "5") (pinfunction "5_5") (pintype "passive"))
    )
    (net (code "235") (name "unconnected-(SV5-Pad6)") (class "Default")
      (node (ref "SV5") (pin "6") (pinfunction "6_6") (pintype "passive"))
    )
    (net (code "236") (name "unconnected-(SV5-Pad7)") (class "Default")
      (node (ref "SV5") (pin "7") (pinfunction "7_7") (pintype "passive"))
    )
    (net (code "237") (name "unconnected-(SV5-Pad8)") (class "Default")
      (node (ref "SV5") (pin "8") (pinfunction "8_8") (pintype "passive"))
    )
    (net (code "238") (name "unconnected-(SV5-Pad9)") (class "Default")
      (node (ref "SV5") (pin "9") (pinfunction "9_9") (pintype "passive"))
    )
    (net (code "239") (name "unconnected-(SV5-Pad10)") (class "Default")
      (node (ref "SV5") (pin "10") (pinfunction "10_10") (pintype "passive"))
    )
    (net (code "240") (name "unconnected-(SV5-Pad11)") (class "Default")
      (node (ref "SV5") (pin "11") (pinfunction "11_11") (pintype "passive"))
    )
    (net (code "241") (name "unconnected-(SV5-Pad12)") (class "Default")
      (node (ref "SV5") (pin "12") (pinfunction "12_12") (pintype "passive"))
    )
    (net (code "242") (name "unconnected-(SV5-Pad13)") (class "Default")
      (node (ref "SV5") (pin "13") (pinfunction "13_13") (pintype "passive"))
    )
    (net (code "243") (name "unconnected-(SV5-Pad14)") (class "Default")
      (node (ref "SV5") (pin "14") (pinfunction "14_14") (pintype "passive"))
    )
    (net (code "244") (name "unconnected-(SV5-Pad15)") (class "Default")
      (node (ref "SV5") (pin "15") (pinfunction "15_15") (pintype "passive"))
    )
    (net (code "245") (name "unconnected-(SV5-Pad16)") (class "Default")
      (node (ref "SV5") (pin "16") (pinfunction "16_16") (pintype "passive"))
    )
    (net (code "246") (name "unconnected-(SV5-Pad17)") (class "Default")
      (node (ref "SV5") (pin "17") (pinfunction "17_17") (pintype "passive"))
    )
    (net (code "247") (name "unconnected-(SV5-Pad19)") (class "Default")
      (node (ref "SV5") (pin "19") (pinfunction "19_19") (pintype "passive"))
    )
    (net (code "248") (name "unconnected-(SV5-Pad20)") (class "Default")
      (node (ref "SV5") (pin "20") (pinfunction "20_20") (pintype "passive"))
    )
    (net (code "249") (name "unconnected-(SV5-Pad21)") (class "Default")
      (node (ref "SV5") (pin "21") (pinfunction "21_21") (pintype "passive"))
    )
    (net (code "250") (name "unconnected-(SV5-Pad23)") (class "Default")
      (node (ref "SV5") (pin "23") (pinfunction "23_23") (pintype "passive"))
    )
    (net (code "251") (name "unconnected-(SV5-Pad24)") (class "Default")
      (node (ref "SV5") (pin "24") (pinfunction "24_24") (pintype "passive"))
    )
    (net (code "252") (name "unconnected-(SV5-Pad25)") (class "Default")
      (node (ref "SV5") (pin "25") (pinfunction "25_25") (pintype "passive"))
    )
    (net (code "253") (name "unconnected-(SV5-Pad26)") (class "Default")
      (node (ref "SV5") (pin "26") (pinfunction "26_26") (pintype "passive"))
    )
    (net (code "254") (name "unconnected-(SV5-Pad27)") (class "Default")
      (node (ref "SV5") (pin "27") (pinfunction "27_27") (pintype "passive"))
    )
    (net (code "255") (name "unconnected-(SV5-Pad28)") (class "Default")
      (node (ref "SV5") (pin "28") (pinfunction "28_28") (pintype "passive"))
    )
    (net (code "256") (name "unconnected-(SV5-Pad29)") (class "Default")
      (node (ref "SV5") (pin "29") (pinfunction "29_29") (pintype "passive"))
    )
    (net (code "257") (name "unconnected-(SV5-Pad30)") (class "Default")
      (node (ref "SV5") (pin "30") (pinfunction "30_30") (pintype "passive"))
    )
    (net (code "258") (name "unconnected-(SV5-Pad31)") (class "Default")
      (node (ref "SV5") (pin "31") (pinfunction "31_31") (pintype "passive"))
    )
    (net (code "259") (name "unconnected-(SV5-Pad33)") (class "Default")
      (node (ref "SV5") (pin "33") (pinfunction "33_33") (pintype "passive"))
    )
    (net (code "260") (name "unconnected-(SV5-Pad35)") (class "Default")
      (node (ref "SV5") (pin "35") (pinfunction "35_35") (pintype "passive"))
    )
    (net (code "261") (name "unconnected-(SV5-Pad36)") (class "Default")
      (node (ref "SV5") (pin "36") (pinfunction "36_36") (pintype "passive"))
    )
    (net (code "262") (name "unconnected-(SV5-Pad38)") (class "Default")
      (node (ref "SV5") (pin "38") (pinfunction "38_38") (pintype "passive"))
    )
    (net (code "263") (name "unconnected-(SV5-Pad43)") (class "Default")
      (node (ref "SV5") (pin "43") (pinfunction "43_43") (pintype "passive"))
    )
    (net (code "264") (name "unconnected-(SV5-Pad44)") (class "Default")
      (node (ref "SV5") (pin "44") (pinfunction "44_44") (pintype "passive"))
    )
    (net (code "265") (name "unconnected-(SV5-Pad45)") (class "Default")
      (node (ref "SV5") (pin "45") (pinfunction "45_45") (pintype "passive"))
    )
    (net (code "266") (name "unconnected-(SV5-Pad46)") (class "Default")
      (node (ref "SV5") (pin "46") (pinfunction "46_46") (pintype "passive"))
    )
    (net (code "267") (name "unconnected-(SV5-Pad47)") (class "Default")
      (node (ref "SV5") (pin "47") (pinfunction "47_47") (pintype "passive"))
    )
    (net (code "268") (name "unconnected-(SV5-Pad48)") (class "Default")
      (node (ref "SV5") (pin "48") (pinfunction "48_48") (pintype "passive"))
    )
  )
)
